# Logic_controller.net
KiCad netlist of a schematic drawn in Altium Designer
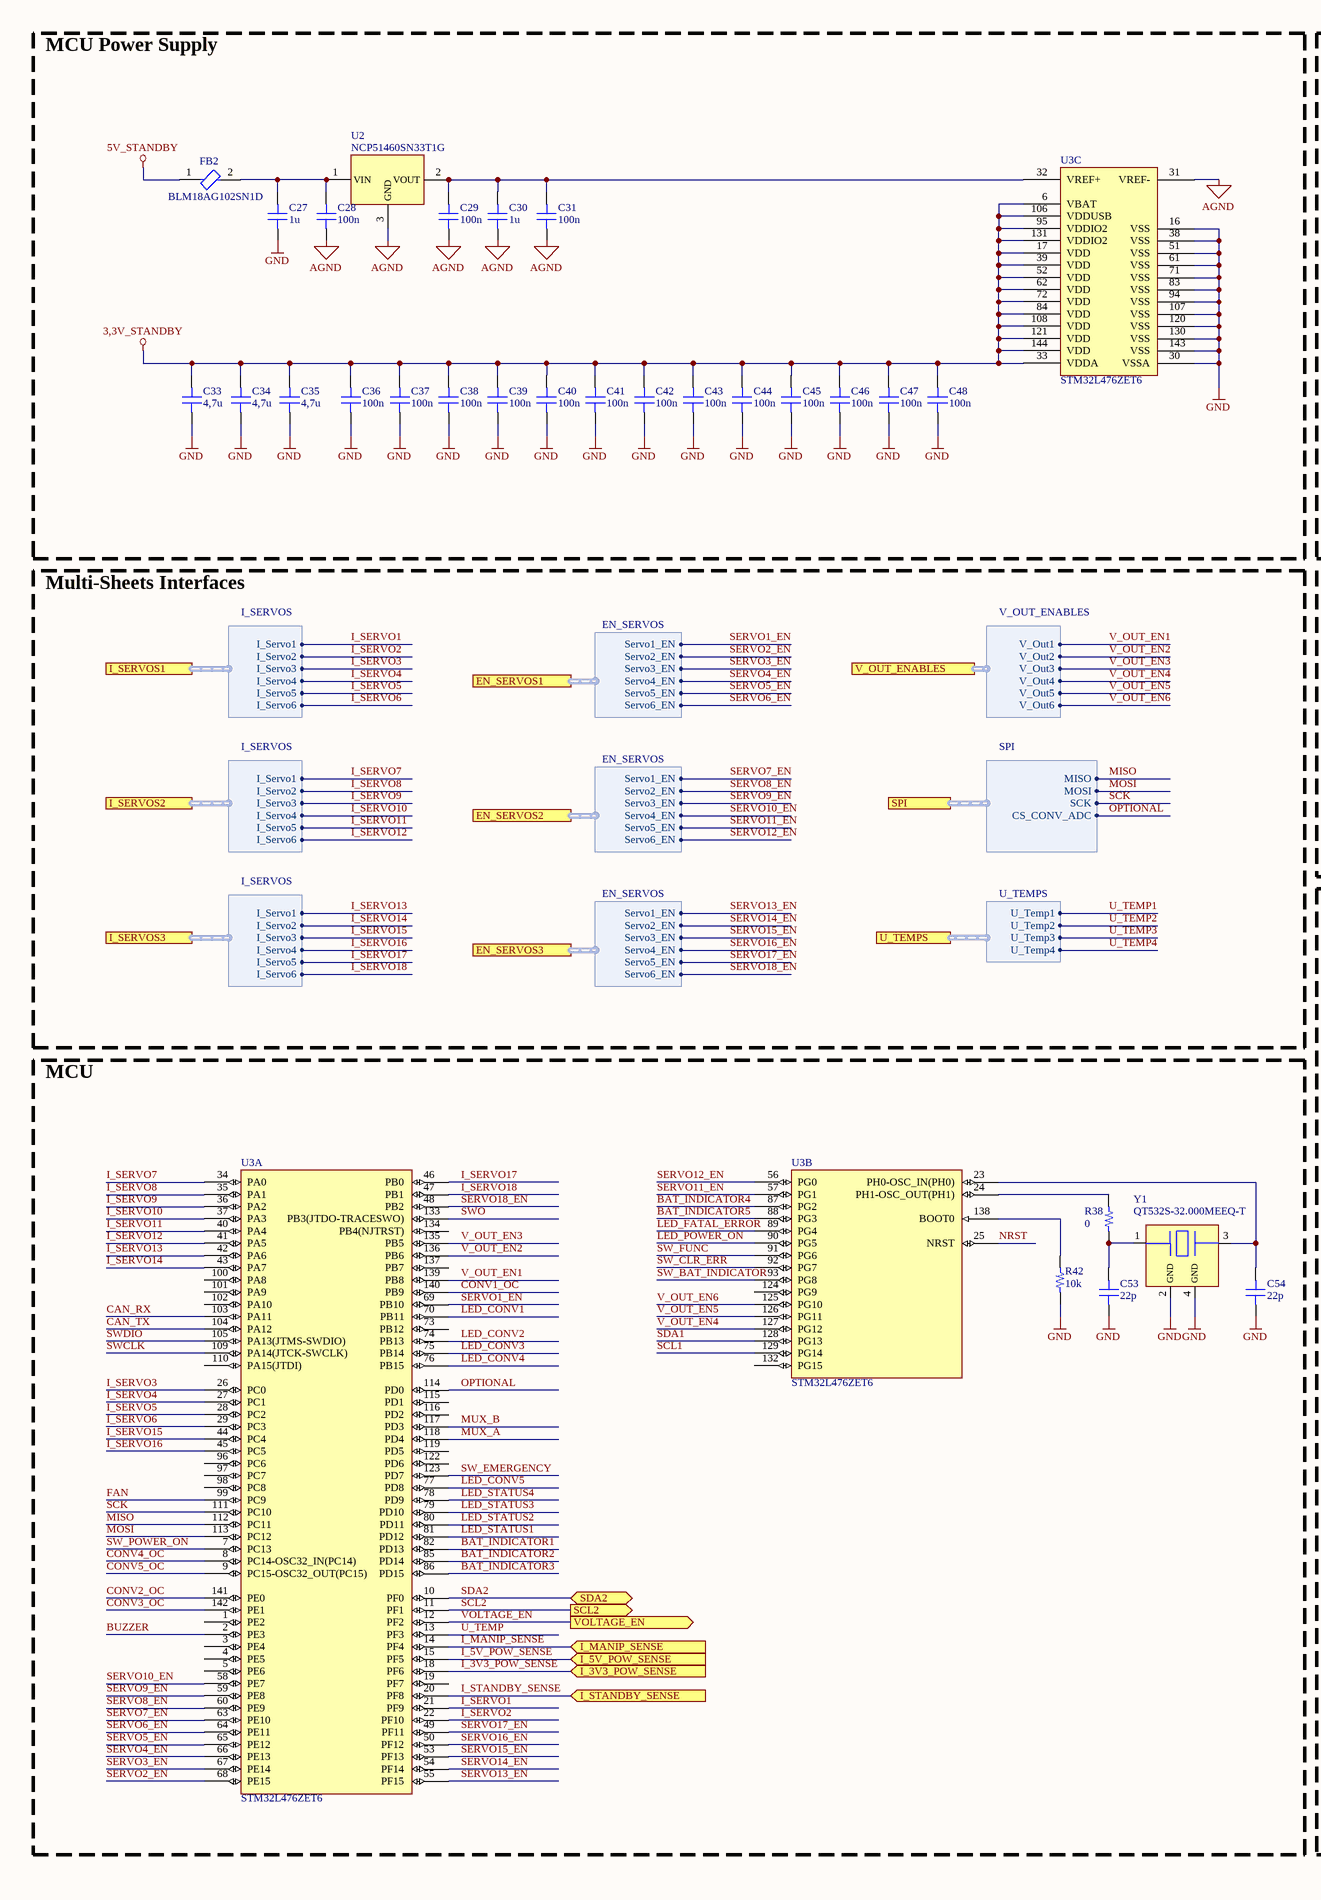
[diagram p0: Logic_controller.SchDoc, left]
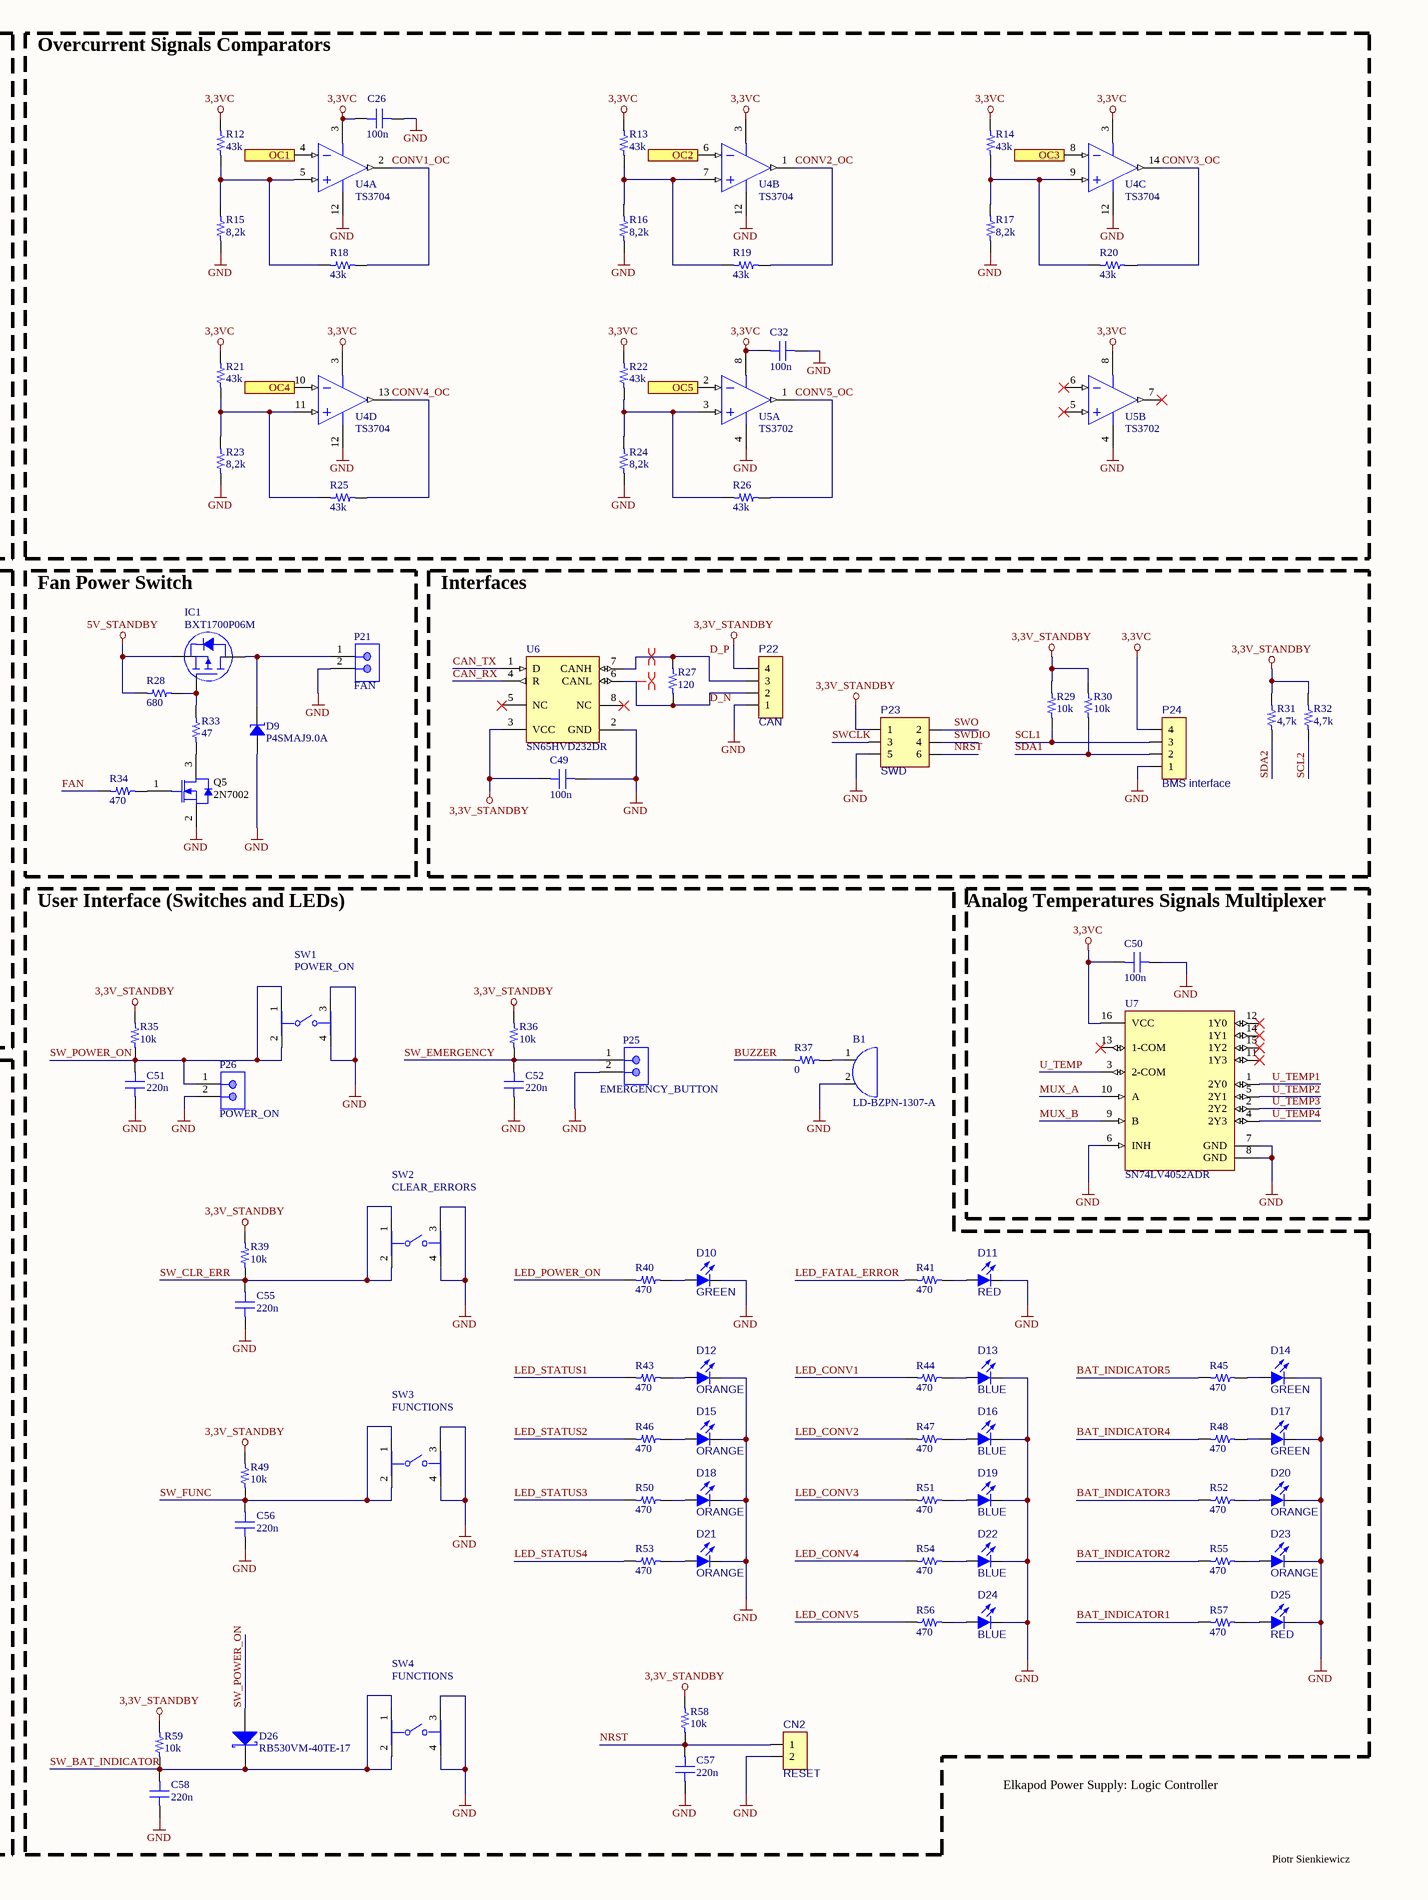
[diagram p1: Logic_controller.SchDoc, right]

(export (version "E")
  (design (tool "Eeschema 10.0.6"))
  (components
    (comp (ref "B1")
      (value "LD-BZPN-1307-A")
      (footprint "LD-BZPN-1307-A")
      (description "12,6mm diameter buzzer without generator; 1-30VAC")
      (libsource (lib "My_passive_components") (part "LD-BZPN-1307-A"))
    )
    (comp (ref "C26")
      (value "100n")
      (footprint "CAP 0603_1608")
      (description "CAP CER 100nF 25V X5R 0603")
      (fields (field (name "PART NUMBER") "C0603C272F3GAC7867") (field (name "MANUFACTURER") "KEMET"))
      (libsource (lib "Celestial Altium Library - altium_library") (part "Capacitor"))
    )
    (comp (ref "C27")
      (value "1u")
      (footprint "CAP 0603_1608")
      (description "CAP CER 1uF 16V X5R 0603")
      (fields (field (name "PART NUMBER") "C0603C272F3GAC7867") (field (name "MANUFACTURER") "KEMET"))
      (libsource (lib "Celestial Altium Library - altium_library") (part "Capacitor"))
    )
    (comp (ref "C28")
      (value "100n")
      (footprint "CAP 0603_1608")
      (description "CAP CER 100nF 25V X5R 0603")
      (fields (field (name "PART NUMBER") "C0603C272F3GAC7867") (field (name "MANUFACTURER") "KEMET"))
      (libsource (lib "Celestial Altium Library - altium_library") (part "Capacitor"))
    )
    (comp (ref "C29")
      (value "100n")
      (footprint "CAP 0603_1608")
      (description "CAP CER 100nF 25V X5R 0603")
      (fields (field (name "PART NUMBER") "C0603C272F3GAC7867") (field (name "MANUFACTURER") "KEMET"))
      (libsource (lib "Celestial Altium Library - altium_library") (part "Capacitor"))
    )
    (comp (ref "C30")
      (value "1u")
      (footprint "CAP 0603_1608")
      (description "CAP CER 1uF 16V X5R 0603")
      (fields (field (name "PART NUMBER") "C0603C272F3GAC7867") (field (name "MANUFACTURER") "KEMET"))
      (libsource (lib "Celestial Altium Library - altium_library") (part "Capacitor"))
    )
    (comp (ref "C31")
      (value "100n")
      (footprint "CAP 0603_1608")
      (description "CAP CER 100nF 25V X5R 0603")
      (fields (field (name "PART NUMBER") "C0603C272F3GAC7867") (field (name "MANUFACTURER") "KEMET"))
      (libsource (lib "Celestial Altium Library - altium_library") (part "Capacitor"))
    )
    (comp (ref "C32")
      (value "100n")
      (footprint "CAP 0603_1608")
      (description "CAP CER 100nF 25V X5R 0603")
      (fields (field (name "PART NUMBER") "C0603C272F3GAC7867") (field (name "MANUFACTURER") "KEMET"))
      (libsource (lib "Celestial Altium Library - altium_library") (part "Capacitor"))
    )
    (comp (ref "C33")
      (value "4,7u")
      (footprint "CAP 0603_1608")
      (description "CAP CER 4,7uF 25V X5R 0603")
      (fields (field (name "PART NUMBER") "C0603C272F3GAC7867") (field (name "MANUFACTURER") "KEMET"))
      (libsource (lib "Celestial Altium Library - altium_library") (part "Capacitor"))
    )
    (comp (ref "C34")
      (value "4,7u")
      (footprint "CAP 0603_1608")
      (description "CAP CER 4,7uF 25V X5R 0603")
      (fields (field (name "PART NUMBER") "C0603C272F3GAC7867") (field (name "MANUFACTURER") "KEMET"))
      (libsource (lib "Celestial Altium Library - altium_library") (part "Capacitor"))
    )
    (comp (ref "C35")
      (value "4,7u")
      (footprint "CAP 0603_1608")
      (description "CAP CER 4,7uF 25V X5R 0603")
      (fields (field (name "PART NUMBER") "C0603C272F3GAC7867") (field (name "MANUFACTURER") "KEMET"))
      (libsource (lib "Celestial Altium Library - altium_library") (part "Capacitor"))
    )
    (comp (ref "C36")
      (value "100n")
      (footprint "CAP 0603_1608")
      (description "CAP CER 100nF 25V X5R 0603")
      (fields (field (name "PART NUMBER") "C0603C272F3GAC7867") (field (name "MANUFACTURER") "KEMET"))
      (libsource (lib "Celestial Altium Library - altium_library") (part "Capacitor"))
    )
    (comp (ref "C37")
      (value "100n")
      (footprint "CAP 0603_1608")
      (description "CAP CER 100nF 25V X5R 0603")
      (fields (field (name "PART NUMBER") "C0603C272F3GAC7867") (field (name "MANUFACTURER") "KEMET"))
      (libsource (lib "Celestial Altium Library - altium_library") (part "Capacitor"))
    )
    (comp (ref "C38")
      (value "100n")
      (footprint "CAP 0603_1608")
      (description "CAP CER 100nF 25V X5R 0603")
      (fields (field (name "PART NUMBER") "C0603C272F3GAC7867") (field (name "MANUFACTURER") "KEMET"))
      (libsource (lib "Celestial Altium Library - altium_library") (part "Capacitor"))
    )
    (comp (ref "C39")
      (value "100n")
      (footprint "CAP 0603_1608")
      (description "CAP CER 100nF 25V X5R 0603")
      (fields (field (name "PART NUMBER") "C0603C272F3GAC7867") (field (name "MANUFACTURER") "KEMET"))
      (libsource (lib "Celestial Altium Library - altium_library") (part "Capacitor"))
    )
    (comp (ref "C40")
      (value "100n")
      (footprint "CAP 0603_1608")
      (description "CAP CER 100nF 25V X5R 0603")
      (fields (field (name "PART NUMBER") "C0603C272F3GAC7867") (field (name "MANUFACTURER") "KEMET"))
      (libsource (lib "Celestial Altium Library - altium_library") (part "Capacitor"))
    )
    (comp (ref "C41")
      (value "100n")
      (footprint "CAP 0603_1608")
      (description "CAP CER 100nF 25V X5R 0603")
      (fields (field (name "PART NUMBER") "C0603C272F3GAC7867") (field (name "MANUFACTURER") "KEMET"))
      (libsource (lib "Celestial Altium Library - altium_library") (part "Capacitor"))
    )
    (comp (ref "C42")
      (value "100n")
      (footprint "CAP 0603_1608")
      (description "CAP CER 100nF 25V X5R 0603")
      (fields (field (name "PART NUMBER") "C0603C272F3GAC7867") (field (name "MANUFACTURER") "KEMET"))
      (libsource (lib "Celestial Altium Library - altium_library") (part "Capacitor"))
    )
    (comp (ref "C43")
      (value "100n")
      (footprint "CAP 0603_1608")
      (description "CAP CER 100nF 25V X5R 0603")
      (fields (field (name "PART NUMBER") "C0603C272F3GAC7867") (field (name "MANUFACTURER") "KEMET"))
      (libsource (lib "Celestial Altium Library - altium_library") (part "Capacitor"))
    )
    (comp (ref "C44")
      (value "100n")
      (footprint "CAP 0603_1608")
      (description "CAP CER 100nF 25V X5R 0603")
      (fields (field (name "PART NUMBER") "C0603C272F3GAC7867") (field (name "MANUFACTURER") "KEMET"))
      (libsource (lib "Celestial Altium Library - altium_library") (part "Capacitor"))
    )
    (comp (ref "C45")
      (value "100n")
      (footprint "CAP 0603_1608")
      (description "CAP CER 100nF 25V X5R 0603")
      (fields (field (name "PART NUMBER") "C0603C272F3GAC7867") (field (name "MANUFACTURER") "KEMET"))
      (libsource (lib "Celestial Altium Library - altium_library") (part "Capacitor"))
    )
    (comp (ref "C46")
      (value "100n")
      (footprint "CAP 0603_1608")
      (description "CAP CER 100nF 25V X5R 0603")
      (fields (field (name "PART NUMBER") "C0603C272F3GAC7867") (field (name "MANUFACTURER") "KEMET"))
      (libsource (lib "Celestial Altium Library - altium_library") (part "Capacitor"))
    )
    (comp (ref "C47")
      (value "100n")
      (footprint "CAP 0603_1608")
      (description "CAP CER 100nF 25V X5R 0603")
      (fields (field (name "PART NUMBER") "C0603C272F3GAC7867") (field (name "MANUFACTURER") "KEMET"))
      (libsource (lib "Celestial Altium Library - altium_library") (part "Capacitor"))
    )
    (comp (ref "C48")
      (value "100n")
      (footprint "CAP 0603_1608")
      (description "CAP CER 100nF 25V X5R 0603")
      (fields (field (name "PART NUMBER") "C0603C272F3GAC7867") (field (name "MANUFACTURER") "KEMET"))
      (libsource (lib "Celestial Altium Library - altium_library") (part "Capacitor"))
    )
    (comp (ref "C49")
      (value "100n")
      (footprint "CAP 0603_1608")
      (description "CAP CER 100nF 25V X5R 0603")
      (fields (field (name "PART NUMBER") "C0603C272F3GAC7867") (field (name "MANUFACTURER") "KEMET"))
      (libsource (lib "Celestial Altium Library - altium_library") (part "Capacitor"))
    )
    (comp (ref "C50")
      (value "100n")
      (footprint "CAP 0603_1608")
      (description "CAP CER 100nF 25V X5R 0603")
      (fields (field (name "PART NUMBER") "C0603C272F3GAC7867") (field (name "MANUFACTURER") "KEMET"))
      (libsource (lib "Celestial Altium Library - altium_library") (part "Capacitor"))
    )
    (comp (ref "C51")
      (value "220n")
      (footprint "CAP 0603_1608")
      (description "CAP CER 220nF 25V X5R 0603")
      (fields (field (name "PART NUMBER") "C0603C272F3GAC7867") (field (name "MANUFACTURER") "KEMET"))
      (libsource (lib "Celestial Altium Library - altium_library") (part "Capacitor"))
    )
    (comp (ref "C52")
      (value "220n")
      (footprint "CAP 0603_1608")
      (description "CAP CER 220nF 25V X5R 0603")
      (fields (field (name "PART NUMBER") "C0603C272F3GAC7867") (field (name "MANUFACTURER") "KEMET"))
      (libsource (lib "Celestial Altium Library - altium_library") (part "Capacitor"))
    )
    (comp (ref "C53")
      (value "22p")
      (footprint "CAP 0603_1608")
      (description "CAP CER 22pF 50V G0C 0603")
      (fields (field (name "PART NUMBER") "C0603C272F3GAC7867") (field (name "MANUFACTURER") "KEMET"))
      (libsource (lib "Celestial Altium Library - altium_library") (part "Capacitor"))
    )
    (comp (ref "C54")
      (value "22p")
      (footprint "CAP 0603_1608")
      (description "CAP CER 22pF 50V G0C 0603")
      (fields (field (name "PART NUMBER") "C0603C272F3GAC7867") (field (name "MANUFACTURER") "KEMET"))
      (libsource (lib "Celestial Altium Library - altium_library") (part "Capacitor"))
    )
    (comp (ref "C55")
      (value "220n")
      (footprint "CAP 0603_1608")
      (description "CAP CER 220nF 25V X5R 0603")
      (fields (field (name "PART NUMBER") "C0603C272F3GAC7867") (field (name "MANUFACTURER") "KEMET"))
      (libsource (lib "Celestial Altium Library - altium_library") (part "Capacitor"))
    )
    (comp (ref "C56")
      (value "220n")
      (footprint "CAP 0603_1608")
      (description "CAP CER 220nF 25V X5R 0603")
      (fields (field (name "PART NUMBER") "C0603C272F3GAC7867") (field (name "MANUFACTURER") "KEMET"))
      (libsource (lib "Celestial Altium Library - altium_library") (part "Capacitor"))
    )
    (comp (ref "C57")
      (value "220n")
      (footprint "CAP 0603_1608")
      (description "CAP CER 220nF 25V X5R 0603")
      (fields (field (name "PART NUMBER") "C0603C272F3GAC7867") (field (name "MANUFACTURER") "KEMET"))
      (libsource (lib "Celestial Altium Library - altium_library") (part "Capacitor"))
    )
    (comp (ref "C58")
      (value "220n")
      (footprint "CAP 0603_1608")
      (description "CAP CER 220nF 25V X5R 0603")
      (fields (field (name "PART NUMBER") "C0603C272F3GAC7867") (field (name "MANUFACTURER") "KEMET"))
      (libsource (lib "Celestial Altium Library - altium_library") (part "Capacitor"))
    )
    (comp (ref "CN2") (value "RESET") (footprint "GP_2x1") (libsource (lib "goldpin_male") (part "CN_2x1")))
    (comp (ref "D9")
      (value "P4SMAJ9.0A")
      (footprint "DO214AC SMA")
      (description "TVS DIODE 9VDC DO214AC")
      (libsource (lib "Celestial Altium Library - altium_library") (part "DIODE TVS UNI"))
    )
    (comp (ref "D10")
      (value "GREEN")
      (footprint "LED0805B")
      (description "GREEN LED")
      (libsource (lib "leds") (part "LED_BLUE"))
    )
    (comp (ref "D11")
      (value "RED")
      (footprint "LED0805B")
      (description "RED LED")
      (libsource (lib "leds") (part "LED_BLUE"))
    )
    (comp (ref "D12")
      (value "ORANGE")
      (footprint "LED0805B")
      (description "ORANGE LED")
      (libsource (lib "leds") (part "LED_BLUE"))
    )
    (comp (ref "D13")
      (value "BLUE")
      (footprint "LED0805B")
      (description "BLUE LED")
      (libsource (lib "leds") (part "LED_BLUE"))
    )
    (comp (ref "D14")
      (value "GREEN")
      (footprint "LED0805B")
      (description "GREEN LED")
      (libsource (lib "leds") (part "LED_BLUE"))
    )
    (comp (ref "D15")
      (value "ORANGE")
      (footprint "LED0805B")
      (description "ORANGE LED")
      (libsource (lib "leds") (part "LED_BLUE"))
    )
    (comp (ref "D16")
      (value "BLUE")
      (footprint "LED0805B")
      (description "BLUE LED")
      (libsource (lib "leds") (part "LED_BLUE"))
    )
    (comp (ref "D17")
      (value "GREEN")
      (footprint "LED0805B")
      (description "GREEN LED")
      (libsource (lib "leds") (part "LED_BLUE"))
    )
    (comp (ref "D18")
      (value "ORANGE")
      (footprint "LED0805B")
      (description "ORANGE LED")
      (libsource (lib "leds") (part "LED_BLUE"))
    )
    (comp (ref "D19")
      (value "BLUE")
      (footprint "LED0805B")
      (description "BLUE LED")
      (libsource (lib "leds") (part "LED_BLUE"))
    )
    (comp (ref "D20")
      (value "ORANGE")
      (footprint "LED0805B")
      (description "ORANGE LED")
      (libsource (lib "leds") (part "LED_BLUE"))
    )
    (comp (ref "D21")
      (value "ORANGE")
      (footprint "LED0805B")
      (description "ORANGE LED")
      (libsource (lib "leds") (part "LED_BLUE"))
    )
    (comp (ref "D22")
      (value "BLUE")
      (footprint "LED0805B")
      (description "BLUE LED")
      (libsource (lib "leds") (part "LED_BLUE"))
    )
    (comp (ref "D23")
      (value "ORANGE")
      (footprint "LED0805B")
      (description "ORANGE LED")
      (libsource (lib "leds") (part "LED_BLUE"))
    )
    (comp (ref "D24")
      (value "BLUE")
      (footprint "LED0805B")
      (description "BLUE LED")
      (libsource (lib "leds") (part "LED_BLUE"))
    )
    (comp (ref "D25")
      (value "RED")
      (footprint "LED0805B")
      (description "RED LED")
      (libsource (lib "leds") (part "LED_BLUE"))
    )
    (comp (ref "D26")
      (value "RB530VM-40TE-17")
      (footprint "SOD-323")
      (description "Schottky diode; 0,1A; 40V")
      (fields (field (name "PUBLISHER") "Altium Limited"))
      (libsource (lib "Infineon Discrete Diode") (part "BAS140W"))
    )
    (comp (ref "FB2")
      (value "BLM18AG102SN1D")
      (footprint "FP-BLM18-0_15-t0_8-MFG")
      (description "Chip Ferrite Bead, 0603, 1000Ω @ 100MHz, 0.5Ω, 25%, 450mA")
      (fields (field (name "TOLERANCE") "25%"))
      (libsource (lib "Altium Content Vault") (part "5f30dd21d616792df468990f7003faa"))
    )
    (comp (ref "IC1")
      (value "BXT1700P06M")
      (footprint "ON SEMI SOT-23-3")
      (description "MOSFET P-CH 60V 2.8A SOT-23-3")
      (libsource (lib "Celestial Altium Library - altium_library") (part "ON SEMI MOSFET P-CH SOT-23-3"))
    )
    (comp (ref "P21")
      (value "FAN")
      (footprint "MOLX-22-23-2021_V")
      (fields (field (name "PARTNUMBER") "22-23-2021"))
      (libsource (lib "Altium Content Vault") (part "CN-1P-M-R2"))
    )
    (comp (ref "P22")
      (value "CAN")
      (footprint "KK/2.54/4")
      (description "Connector: PCB-cable; KK; socket; male; PIN:4; straight/right-angle; tinned; THT")
      (libsource (lib "kk") (part "CN_4x1"))
    )
    (comp (ref "P23") (value "SWD") (footprint "GP_3x2") (libsource (lib "goldpin_male") (part "CN_3x2")))
    (comp (ref "P24")
      (value "BMS interface")
      (footprint "KK/2.54/4")
      (description "Connector: PCB-cable; KK; socket; male; PIN:4; straight/right-angle; tinned; THT")
      (libsource (lib "kk") (part "CN_4x1"))
    )
    (comp (ref "P25")
      (value "EMERGENCY_BUTTON")
      (footprint "MOLX-22-23-2021_V")
      (fields (field (name "PARTNUMBER") "22-23-2021"))
      (libsource (lib "Altium Content Vault") (part "CN-1P-M-R2"))
    )
    (comp (ref "P26")
      (value "POWER_ON")
      (footprint "MOLX-22-23-2021_V")
      (fields (field (name "PARTNUMBER") "22-23-2021"))
      (libsource (lib "Altium Content Vault") (part "CN-1P-M-R2"))
    )
    (comp (ref "Q5")
      (value "2N7002")
      (footprint "INF-PG-SOT23_M")
      (fields (field (name "MANUFACTURER") "Infineon"))
      (libsource (lib "Altium Content Vault") (part "INF-NDMOS-GSD-3"))
    )
    (comp (ref "R12")
      (value "43k")
      (footprint "RES 0603_1608")
      (description "RES 43K OHM 1% 0,1W 0603")
      (fields
        (field (name "PART NUMBER") "RNCS0603BKE10K0")
        (field (name "MANUFACTURER") "Stackpole Electronics Inc")
      )
      (libsource (lib "Celestial Altium Library - altium_library") (part "Resistor"))
    )
    (comp (ref "R13")
      (value "43k")
      (footprint "RES 0603_1608")
      (description "RES 43K OHM 1% 0,1W 0603")
      (fields
        (field (name "PART NUMBER") "RNCS0603BKE10K0")
        (field (name "MANUFACTURER") "Stackpole Electronics Inc")
      )
      (libsource (lib "Celestial Altium Library - altium_library") (part "Resistor"))
    )
    (comp (ref "R14")
      (value "43k")
      (footprint "RES 0603_1608")
      (description "RES 43K OHM 1% 0,1W 0603")
      (fields
        (field (name "PART NUMBER") "RNCS0603BKE10K0")
        (field (name "MANUFACTURER") "Stackpole Electronics Inc")
      )
      (libsource (lib "Celestial Altium Library - altium_library") (part "Resistor"))
    )
    (comp (ref "R15")
      (value "8,2k")
      (footprint "RES 0603_1608")
      (description "RES 8,2K OHM 1% 0,1W 0603")
      (fields
        (field (name "PART NUMBER") "RNCS0603BKE10K0")
        (field (name "MANUFACTURER") "Stackpole Electronics Inc")
      )
      (libsource (lib "Celestial Altium Library - altium_library") (part "Resistor"))
    )
    (comp (ref "R16")
      (value "8,2k")
      (footprint "RES 0603_1608")
      (description "RES 8,2K OHM 1% 0,1W 0603")
      (fields
        (field (name "PART NUMBER") "RNCS0603BKE10K0")
        (field (name "MANUFACTURER") "Stackpole Electronics Inc")
      )
      (libsource (lib "Celestial Altium Library - altium_library") (part "Resistor"))
    )
    (comp (ref "R17")
      (value "8,2k")
      (footprint "RES 0603_1608")
      (description "RES 8,2K OHM 1% 0,1W 0603")
      (fields
        (field (name "PART NUMBER") "RNCS0603BKE10K0")
        (field (name "MANUFACTURER") "Stackpole Electronics Inc")
      )
      (libsource (lib "Celestial Altium Library - altium_library") (part "Resistor"))
    )
    (comp (ref "R18")
      (value "43k")
      (footprint "RES 0603_1608")
      (description "RES 43K OHM 1% 0,1W 0603")
      (fields
        (field (name "PART NUMBER") "RNCS0603BKE10K0")
        (field (name "MANUFACTURER") "Stackpole Electronics Inc")
      )
      (libsource (lib "Celestial Altium Library - altium_library") (part "Resistor"))
    )
    (comp (ref "R19")
      (value "43k")
      (footprint "RES 0603_1608")
      (description "RES 43K OHM 1% 0,1W 0603")
      (fields
        (field (name "PART NUMBER") "RNCS0603BKE10K0")
        (field (name "MANUFACTURER") "Stackpole Electronics Inc")
      )
      (libsource (lib "Celestial Altium Library - altium_library") (part "Resistor"))
    )
    (comp (ref "R20")
      (value "43k")
      (footprint "RES 0603_1608")
      (description "RES 43K OHM 1% 0,1W 0603")
      (fields
        (field (name "PART NUMBER") "RNCS0603BKE10K0")
        (field (name "MANUFACTURER") "Stackpole Electronics Inc")
      )
      (libsource (lib "Celestial Altium Library - altium_library") (part "Resistor"))
    )
    (comp (ref "R21")
      (value "43k")
      (footprint "RES 0603_1608")
      (description "RES 43K OHM 1% 0,1W 0603")
      (fields
        (field (name "PART NUMBER") "RNCS0603BKE10K0")
        (field (name "MANUFACTURER") "Stackpole Electronics Inc")
      )
      (libsource (lib "Celestial Altium Library - altium_library") (part "Resistor"))
    )
    (comp (ref "R22")
      (value "43k")
      (footprint "RES 0603_1608")
      (description "RES 43K OHM 1% 0,1W 0603")
      (fields
        (field (name "PART NUMBER") "RNCS0603BKE10K0")
        (field (name "MANUFACTURER") "Stackpole Electronics Inc")
      )
      (libsource (lib "Celestial Altium Library - altium_library") (part "Resistor"))
    )
    (comp (ref "R23")
      (value "8,2k")
      (footprint "RES 0603_1608")
      (description "RES 8,2K OHM 1% 0,1W 0603")
      (fields
        (field (name "PART NUMBER") "RNCS0603BKE10K0")
        (field (name "MANUFACTURER") "Stackpole Electronics Inc")
      )
      (libsource (lib "Celestial Altium Library - altium_library") (part "Resistor"))
    )
    (comp (ref "R24")
      (value "8,2k")
      (footprint "RES 0603_1608")
      (description "RES 8,2K OHM 1% 0,1W 0603")
      (fields
        (field (name "PART NUMBER") "RNCS0603BKE10K0")
        (field (name "MANUFACTURER") "Stackpole Electronics Inc")
      )
      (libsource (lib "Celestial Altium Library - altium_library") (part "Resistor"))
    )
    (comp (ref "R25")
      (value "43k")
      (footprint "RES 0603_1608")
      (description "RES 43K OHM 1% 0,1W 0603")
      (fields
        (field (name "PART NUMBER") "RNCS0603BKE10K0")
        (field (name "MANUFACTURER") "Stackpole Electronics Inc")
      )
      (libsource (lib "Celestial Altium Library - altium_library") (part "Resistor"))
    )
    (comp (ref "R26")
      (value "43k")
      (footprint "RES 0603_1608")
      (description "RES 43K OHM 1% 0,1W 0603")
      (fields
        (field (name "PART NUMBER") "RNCS0603BKE10K0")
        (field (name "MANUFACTURER") "Stackpole Electronics Inc")
      )
      (libsource (lib "Celestial Altium Library - altium_library") (part "Resistor"))
    )
    (comp (ref "R27")
      (value "120")
      (footprint "RES 0603_1608")
      (description "RES 120 OHM 1% 0,1W 0603")
      (fields
        (field (name "PART NUMBER") "RNCS0603BKE10K0")
        (field (name "MANUFACTURER") "Stackpole Electronics Inc")
      )
      (libsource (lib "Celestial Altium Library - altium_library") (part "Resistor"))
    )
    (comp (ref "R28")
      (value "680")
      (footprint "RES 0603_1608")
      (description "RES 680 OHM 1% 0,1W 0603")
      (fields
        (field (name "PART NUMBER") "RNCS0603BKE10K0")
        (field (name "MANUFACTURER") "Stackpole Electronics Inc")
      )
      (libsource (lib "Celestial Altium Library - altium_library") (part "Resistor"))
    )
    (comp (ref "R29")
      (value "10k")
      (footprint "RES 0603_1608")
      (description "RES 10K OHM 1% 0,1W 0603")
      (fields
        (field (name "PART NUMBER") "RNCS0603BKE10K0")
        (field (name "MANUFACTURER") "Stackpole Electronics Inc")
      )
      (libsource (lib "Celestial Altium Library - altium_library") (part "Resistor"))
    )
    (comp (ref "R30")
      (value "10k")
      (footprint "RES 0603_1608")
      (description "RES 10K OHM 1% 0,1W 0603")
      (fields
        (field (name "PART NUMBER") "RNCS0603BKE10K0")
        (field (name "MANUFACTURER") "Stackpole Electronics Inc")
      )
      (libsource (lib "Celestial Altium Library - altium_library") (part "Resistor"))
    )
    (comp (ref "R31")
      (value "4,7k")
      (footprint "RES 0603_1608")
      (description "RES 4,7K OHM 1% 0,1W 0603")
      (fields
        (field (name "PART NUMBER") "RNCS0603BKE10K0")
        (field (name "MANUFACTURER") "Stackpole Electronics Inc")
      )
      (libsource (lib "Celestial Altium Library - altium_library") (part "Resistor"))
    )
    (comp (ref "R32")
      (value "4,7k")
      (footprint "RES 0603_1608")
      (description "RES 4,7K OHM 1% 0,1W 0603")
      (fields
        (field (name "PART NUMBER") "RNCS0603BKE10K0")
        (field (name "MANUFACTURER") "Stackpole Electronics Inc")
      )
      (libsource (lib "Celestial Altium Library - altium_library") (part "Resistor"))
    )
    (comp (ref "R33")
      (value "47")
      (footprint "RES 0603_1608")
      (description "RES 47 OHM 1% 0,1W 0603")
      (fields
        (field (name "PART NUMBER") "RNCS0603BKE10K0")
        (field (name "MANUFACTURER") "Stackpole Electronics Inc")
      )
      (libsource (lib "Celestial Altium Library - altium_library") (part "Resistor"))
    )
    (comp (ref "R34")
      (value "470")
      (footprint "RES 0603_1608")
      (description "RES 470 OHM 1% 0,1W 0603")
      (fields
        (field (name "PART NUMBER") "RNCS0603BKE10K0")
        (field (name "MANUFACTURER") "Stackpole Electronics Inc")
      )
      (libsource (lib "Celestial Altium Library - altium_library") (part "Resistor"))
    )
    (comp (ref "R35")
      (value "10k")
      (footprint "RES 0603_1608")
      (description "RES 10K OHM 1% 0,1W 0603")
      (fields
        (field (name "PART NUMBER") "RNCS0603BKE10K0")
        (field (name "MANUFACTURER") "Stackpole Electronics Inc")
      )
      (libsource (lib "Celestial Altium Library - altium_library") (part "Resistor"))
    )
    (comp (ref "R36")
      (value "10k")
      (footprint "RES 0603_1608")
      (description "RES 10K OHM 1% 0,1W 0603")
      (fields
        (field (name "PART NUMBER") "RNCS0603BKE10K0")
        (field (name "MANUFACTURER") "Stackpole Electronics Inc")
      )
      (libsource (lib "Celestial Altium Library - altium_library") (part "Resistor"))
    )
    (comp (ref "R37")
      (value "0")
      (footprint "RES 0603_1608")
      (description "RES 0 OHM 1% 0,1W 0603")
      (fields
        (field (name "PART NUMBER") "RNCS0603BKE10K0")
        (field (name "MANUFACTURER") "Stackpole Electronics Inc")
      )
      (libsource (lib "Celestial Altium Library - altium_library") (part "Resistor"))
    )
    (comp (ref "R38")
      (value "0")
      (footprint "RES 0603_1608")
      (description "RES 0 OHM 1% 0,1W 0603")
      (fields
        (field (name "PART NUMBER") "RNCS0603BKE10K0")
        (field (name "MANUFACTURER") "Stackpole Electronics Inc")
      )
      (libsource (lib "Celestial Altium Library - altium_library") (part "Resistor"))
    )
    (comp (ref "R39")
      (value "10k")
      (footprint "RES 0603_1608")
      (description "RES 10K OHM 1% 0,1W 0603")
      (fields
        (field (name "PART NUMBER") "RNCS0603BKE10K0")
        (field (name "MANUFACTURER") "Stackpole Electronics Inc")
      )
      (libsource (lib "Celestial Altium Library - altium_library") (part "Resistor"))
    )
    (comp (ref "R40")
      (value "470")
      (footprint "RES 0603_1608")
      (description "RES 470 OHM 1% 0,1W 0603")
      (fields
        (field (name "PART NUMBER") "RNCS0603BKE10K0")
        (field (name "MANUFACTURER") "Stackpole Electronics Inc")
      )
      (libsource (lib "Celestial Altium Library - altium_library") (part "Resistor"))
    )
    (comp (ref "R41")
      (value "470")
      (footprint "RES 0603_1608")
      (description "RES 470 OHM 1% 0,1W 0603")
      (fields
        (field (name "PART NUMBER") "RNCS0603BKE10K0")
        (field (name "MANUFACTURER") "Stackpole Electronics Inc")
      )
      (libsource (lib "Celestial Altium Library - altium_library") (part "Resistor"))
    )
    (comp (ref "R42")
      (value "10k")
      (footprint "RES 0603_1608")
      (description "RES 10K OHM 1% 0,1W 0603")
      (fields
        (field (name "PART NUMBER") "RNCS0603BKE10K0")
        (field (name "MANUFACTURER") "Stackpole Electronics Inc")
      )
      (libsource (lib "Celestial Altium Library - altium_library") (part "Resistor"))
    )
    (comp (ref "R43")
      (value "470")
      (footprint "RES 0603_1608")
      (description "RES 470 OHM 1% 0,1W 0603")
      (fields
        (field (name "PART NUMBER") "RNCS0603BKE10K0")
        (field (name "MANUFACTURER") "Stackpole Electronics Inc")
      )
      (libsource (lib "Celestial Altium Library - altium_library") (part "Resistor"))
    )
    (comp (ref "R44")
      (value "470")
      (footprint "RES 0603_1608")
      (description "RES 470 OHM 1% 0,1W 0603")
      (fields
        (field (name "PART NUMBER") "RNCS0603BKE10K0")
        (field (name "MANUFACTURER") "Stackpole Electronics Inc")
      )
      (libsource (lib "Celestial Altium Library - altium_library") (part "Resistor"))
    )
    (comp (ref "R45")
      (value "470")
      (footprint "RES 0603_1608")
      (description "RES 470 OHM 1% 0,1W 0603")
      (fields
        (field (name "PART NUMBER") "RNCS0603BKE10K0")
        (field (name "MANUFACTURER") "Stackpole Electronics Inc")
      )
      (libsource (lib "Celestial Altium Library - altium_library") (part "Resistor"))
    )
    (comp (ref "R46")
      (value "470")
      (footprint "RES 0603_1608")
      (description "RES 470 OHM 1% 0,1W 0603")
      (fields
        (field (name "PART NUMBER") "RNCS0603BKE10K0")
        (field (name "MANUFACTURER") "Stackpole Electronics Inc")
      )
      (libsource (lib "Celestial Altium Library - altium_library") (part "Resistor"))
    )
    (comp (ref "R47")
      (value "470")
      (footprint "RES 0603_1608")
      (description "RES 470 OHM 1% 0,1W 0603")
      (fields
        (field (name "PART NUMBER") "RNCS0603BKE10K0")
        (field (name "MANUFACTURER") "Stackpole Electronics Inc")
      )
      (libsource (lib "Celestial Altium Library - altium_library") (part "Resistor"))
    )
    (comp (ref "R48")
      (value "470")
      (footprint "RES 0603_1608")
      (description "RES 470 OHM 1% 0,1W 0603")
      (fields
        (field (name "PART NUMBER") "RNCS0603BKE10K0")
        (field (name "MANUFACTURER") "Stackpole Electronics Inc")
      )
      (libsource (lib "Celestial Altium Library - altium_library") (part "Resistor"))
    )
    (comp (ref "R49")
      (value "10k")
      (footprint "RES 0603_1608")
      (description "RES 10K OHM 1% 0,1W 0603")
      (fields
        (field (name "PART NUMBER") "RNCS0603BKE10K0")
        (field (name "MANUFACTURER") "Stackpole Electronics Inc")
      )
      (libsource (lib "Celestial Altium Library - altium_library") (part "Resistor"))
    )
    (comp (ref "R50")
      (value "470")
      (footprint "RES 0603_1608")
      (description "RES 470 OHM 1% 0,1W 0603")
      (fields
        (field (name "PART NUMBER") "RNCS0603BKE10K0")
        (field (name "MANUFACTURER") "Stackpole Electronics Inc")
      )
      (libsource (lib "Celestial Altium Library - altium_library") (part "Resistor"))
    )
    (comp (ref "R51")
      (value "470")
      (footprint "RES 0603_1608")
      (description "RES 470 OHM 1% 0,1W 0603")
      (fields
        (field (name "PART NUMBER") "RNCS0603BKE10K0")
        (field (name "MANUFACTURER") "Stackpole Electronics Inc")
      )
      (libsource (lib "Celestial Altium Library - altium_library") (part "Resistor"))
    )
    (comp (ref "R52")
      (value "470")
      (footprint "RES 0603_1608")
      (description "RES 470 OHM 1% 0,1W 0603")
      (fields
        (field (name "PART NUMBER") "RNCS0603BKE10K0")
        (field (name "MANUFACTURER") "Stackpole Electronics Inc")
      )
      (libsource (lib "Celestial Altium Library - altium_library") (part "Resistor"))
    )
    (comp (ref "R53")
      (value "470")
      (footprint "RES 0603_1608")
      (description "RES 470 OHM 1% 0,1W 0603")
      (fields
        (field (name "PART NUMBER") "RNCS0603BKE10K0")
        (field (name "MANUFACTURER") "Stackpole Electronics Inc")
      )
      (libsource (lib "Celestial Altium Library - altium_library") (part "Resistor"))
    )
    (comp (ref "R54")
      (value "470")
      (footprint "RES 0603_1608")
      (description "RES 470 OHM 1% 0,1W 0603")
      (fields
        (field (name "PART NUMBER") "RNCS0603BKE10K0")
        (field (name "MANUFACTURER") "Stackpole Electronics Inc")
      )
      (libsource (lib "Celestial Altium Library - altium_library") (part "Resistor"))
    )
    (comp (ref "R55")
      (value "470")
      (footprint "RES 0603_1608")
      (description "RES 470 OHM 1% 0,1W 0603")
      (fields
        (field (name "PART NUMBER") "RNCS0603BKE10K0")
        (field (name "MANUFACTURER") "Stackpole Electronics Inc")
      )
      (libsource (lib "Celestial Altium Library - altium_library") (part "Resistor"))
    )
    (comp (ref "R56")
      (value "470")
      (footprint "RES 0603_1608")
      (description "RES 470 OHM 1% 0,1W 0603")
      (fields
        (field (name "PART NUMBER") "RNCS0603BKE10K0")
        (field (name "MANUFACTURER") "Stackpole Electronics Inc")
      )
      (libsource (lib "Celestial Altium Library - altium_library") (part "Resistor"))
    )
    (comp (ref "R57")
      (value "470")
      (footprint "RES 0603_1608")
      (description "RES 470 OHM 1% 0,1W 0603")
      (fields
        (field (name "PART NUMBER") "RNCS0603BKE10K0")
        (field (name "MANUFACTURER") "Stackpole Electronics Inc")
      )
      (libsource (lib "Celestial Altium Library - altium_library") (part "Resistor"))
    )
    (comp (ref "R58")
      (value "10k")
      (footprint "RES 0603_1608")
      (description "RES 10K OHM 1% 0,1W 0603")
      (fields
        (field (name "PART NUMBER") "RNCS0603BKE10K0")
        (field (name "MANUFACTURER") "Stackpole Electronics Inc")
      )
      (libsource (lib "Celestial Altium Library - altium_library") (part "Resistor"))
    )
    (comp (ref "R59")
      (value "10k")
      (footprint "RES 0603_1608")
      (description "RES 10K OHM 1% 0,1W 0603")
      (fields
        (field (name "PART NUMBER") "RNCS0603BKE10K0")
        (field (name "MANUFACTURER") "Stackpole Electronics Inc")
      )
      (libsource (lib "Celestial Altium Library - altium_library") (part "Resistor"))
    )
    (comp (ref "SW1")
      (value "POWER_ON")
      (footprint "FP-B3FS-1000-MFG")
      (description "SWITCH TACTILE SPST-NO 0.05A 24V")
      (fields
        (field (name "MANUFACTURER") "Omron Electronics Inc-EMC Div")
        (field (name "OCTOPART") "https://octopart.com/b3fs-1000-omron-116581")
      )
      (libsource (lib "Altium Content Vault") (part "b8895f3f4cefb76e1819d2863dba89b"))
    )
    (comp (ref "SW2")
      (value "CLEAR_ERRORS")
      (footprint "FP-B3FS-1000-MFG")
      (description "SWITCH TACTILE SPST-NO 0.05A 24V")
      (fields
        (field (name "MANUFACTURER") "Omron Electronics Inc-EMC Div")
        (field (name "OCTOPART") "https://octopart.com/b3fs-1000-omron-116581")
      )
      (libsource (lib "Altium Content Vault") (part "b8895f3f4cefb76e1819d2863dba89b"))
    )
    (comp (ref "SW3")
      (value "FUNCTIONS")
      (footprint "FP-B3FS-1000-MFG")
      (description "SWITCH TACTILE SPST-NO 0.05A 24V")
      (fields
        (field (name "MANUFACTURER") "Omron Electronics Inc-EMC Div")
        (field (name "OCTOPART") "https://octopart.com/b3fs-1000-omron-116581")
      )
      (libsource (lib "Altium Content Vault") (part "b8895f3f4cefb76e1819d2863dba89b"))
    )
    (comp (ref "SW4")
      (value "FUNCTIONS")
      (footprint "FP-B3FS-1000-MFG")
      (description "SWITCH TACTILE SPST-NO 0.05A 24V")
      (fields
        (field (name "MANUFACTURER") "Omron Electronics Inc-EMC Div")
        (field (name "OCTOPART") "https://octopart.com/b3fs-1000-omron-116581")
      )
      (libsource (lib "Altium Content Vault") (part "b8895f3f4cefb76e1819d2863dba89b"))
    )
    (comp (ref "U2")
      (value "NCP51460SN33T1G")
      (footprint "SOT23-3")
      (description "Low power precision voltage reference; Iout = 20mA")
      (libsource (lib "My_voltage_regulators") (part "NCP51460SN33T1G"))
    )
    (comp (ref "U3")
      (value "STM32L476ZET6")
      (footprint "STM-LQFP144_M")
      (fields (field (name "MANUFACTURER") "STMicroelectronics"))
      (libsource (lib "Altium Content Vault") (part "MC-ARM-STM32L4X6-LQFP144"))
    )
    (comp (ref "U4")
      (value "TS3704")
      (footprint "SOIC14")
      (description "Micropower push-pusll quad CMOS voltage comparator")
      (libsource (lib "My_integrated_circuits") (part "TS3704"))
    )
    (comp (ref "U5")
      (value "TS3702")
      (footprint "SOIC8")
      (description "Micropower push-pull dual CMOS voltage comparator")
      (libsource (lib "My_integrated_circuits") (part "TS3702"))
    )
    (comp (ref "U6")
      (value "SN65HVD232DR")
      (footprint "D0008A_M")
      (description "3.3 V Can Transceiver, 17 mA, -40 to 85 degC, 8-pin SOIC (D), Green (RoHS & no Sb/Br)")
      (fields (field (name "MANUFACTURER") "Texas Instruments"))
      (libsource (lib "Altium Content Vault") (part "TI-SN65HVD232-SOIC_D-8"))
    )
    (comp (ref "U7")
      (value "SN74LV4052ADR")
      (footprint "FP-D0016A-IPC_B")
      (description "IC MULTIPLEXER DUAL 4X1 16SOIC")
      (libsource (lib "Altium Content Vault") (part "1d2634ae6b0fec4cd987bcefd96d63e"))
    )
    (comp (ref "Y1")
      (value "QT532S-32.000MEEQ-T")
      (footprint "QT532S_5,0x3,2_crystal")
      (libsource (lib "My_passive_components") (part "QT532S_CRYSTAL"))
    )
  )
  (nets
    (net (code "6") (name "/BAT_INDICATOR1") (class "Default")
      (node (ref "R57") (pin "2") (pinfunction "2_2") (pintype "passive"))
      (node (ref "U3") (pin "82") (pinfunction "PD13_82") (pintype "bidirectional"))
    )
    (net (code "7") (name "/BAT_INDICATOR2") (class "Default")
      (node (ref "R55") (pin "2") (pinfunction "2_2") (pintype "passive"))
      (node (ref "U3") (pin "85") (pinfunction "PD14_85") (pintype "bidirectional"))
    )
    (net (code "8") (name "/BAT_INDICATOR3") (class "Default")
      (node (ref "R52") (pin "2") (pinfunction "2_2") (pintype "passive"))
      (node (ref "U3") (pin "86") (pinfunction "PD15_86") (pintype "bidirectional"))
    )
    (net (code "9") (name "/BAT_INDICATOR4") (class "Default")
      (node (ref "R48") (pin "2") (pinfunction "2_2") (pintype "passive"))
      (node (ref "U3") (pin "87") (pinfunction "PG2_87") (pintype "bidirectional"))
    )
    (net (code "10") (name "/BAT_INDICATOR5") (class "Default")
      (node (ref "R45") (pin "2") (pinfunction "2_2") (pintype "passive"))
      (node (ref "U3") (pin "88") (pinfunction "PG3_88") (pintype "bidirectional"))
    )
    (net (code "11") (name "/BUZZER") (class "Default")
      (node (ref "R37") (pin "1") (pinfunction "1_1") (pintype "passive"))
      (node (ref "U3") (pin "2") (pinfunction "PE3_2") (pintype "bidirectional"))
    )
    (net (code "12") (name "/CAN_RX") (class "Default")
      (node (ref "U3") (pin "103") (pinfunction "PA11_103") (pintype "bidirectional"))
      (node (ref "U6") (pin "4") (pinfunction "R_4") (pintype "output"))
    )
    (net (code "13") (name "/CAN_TX") (class "Default")
      (node (ref "U3") (pin "104") (pinfunction "PA12_104") (pintype "bidirectional"))
      (node (ref "U6") (pin "1") (pinfunction "D_1") (pintype "input"))
    )
    (net (code "14") (name "/CONV1_OC") (class "Default")
      (node (ref "R18") (pin "2") (pinfunction "2_2") (pintype "passive"))
      (node (ref "U3") (pin "140") (pinfunction "PB9_140") (pintype "bidirectional"))
      (node (ref "U4") (pin "2") (pinfunction "OUT1_2") (pintype "output"))
    )
    (net (code "15") (name "/CONV2_OC") (class "Default")
      (node (ref "R19") (pin "1") (pinfunction "1_1") (pintype "passive"))
      (node (ref "U3") (pin "141") (pinfunction "PE0_141") (pintype "bidirectional"))
      (node (ref "U4") (pin "1") (pinfunction "OUT2_1") (pintype "output"))
    )
    (net (code "16") (name "/CONV3_OC") (class "Default")
      (node (ref "R20") (pin "1") (pinfunction "1_1") (pintype "passive"))
      (node (ref "U3") (pin "142") (pinfunction "PE1_142") (pintype "bidirectional"))
      (node (ref "U4") (pin "14") (pinfunction "OUT3_14") (pintype "output"))
    )
    (net (code "17") (name "/CONV4_OC") (class "Default")
      (node (ref "R25") (pin "1") (pinfunction "1_1") (pintype "passive"))
      (node (ref "U3") (pin "8") (pinfunction "PC14-OSC32_IN(PC14)_8") (pintype "bidirectional"))
      (node (ref "U4") (pin "13") (pinfunction "OUT4_13") (pintype "output"))
    )
    (net (code "18") (name "/CONV5_OC") (class "Default")
      (node (ref "R26") (pin "1") (pinfunction "1_1") (pintype "passive"))
      (node (ref "U3") (pin "9") (pinfunction "PC15-OSC32_OUT(PC15)_9") (pintype "bidirectional"))
      (node (ref "U5") (pin "1") (pinfunction "OUT1_1") (pintype "output"))
    )
    (net (code "19") (name "/D_N") (class "Default")
      (node (ref "P22") (pin "2") (pinfunction "2_2") (pintype "passive"))
      (node (ref "R27") (pin "2") (pinfunction "2_2") (pintype "passive"))
      (node (ref "U6") (pin "6") (pinfunction "CANL_6") (pintype "bidirectional"))
    )
    (net (code "20") (name "/D_P") (class "Default")
      (node (ref "P22") (pin "3") (pinfunction "3_3") (pintype "passive"))
      (node (ref "R27") (pin "1") (pinfunction "1_1") (pintype "passive"))
      (node (ref "U6") (pin "7") (pinfunction "CANH_7") (pintype "bidirectional"))
    )
    (net (code "21") (name "/FAN") (class "Default")
      (node (ref "R34") (pin "1") (pinfunction "1_1") (pintype "passive"))
      (node (ref "U3") (pin "99") (pinfunction "PC9_99") (pintype "bidirectional"))
    )
    (net (code "22") (name "/I_3V3_POW_SENSE") (class "Default")
      (node (ref "U3") (pin "18") (pinfunction "PF6_18") (pintype "bidirectional"))
    )
    (net (code "23") (name "/I_5V_POW_SENSE") (class "Default")
      (node (ref "U3") (pin "15") (pinfunction "PF5_15") (pintype "bidirectional"))
    )
    (net (code "24") (name "/I_MANIP_SENSE") (class "Default")
      (node (ref "U3") (pin "14") (pinfunction "PF4_14") (pintype "bidirectional"))
    )
    (net (code "25") (name "/I_SERVO1") (class "Default")
      (node (ref "U3") (pin "21") (pinfunction "PF9_21") (pintype "bidirectional"))
    )
    (net (code "26") (name "/I_SERVO2") (class "Default")
      (node (ref "U3") (pin "22") (pinfunction "PF10_22") (pintype "bidirectional"))
    )
    (net (code "27") (name "/I_SERVO3") (class "Default")
      (node (ref "U3") (pin "26") (pinfunction "PC0_26") (pintype "bidirectional"))
    )
    (net (code "28") (name "/I_SERVO4") (class "Default")
      (node (ref "U3") (pin "27") (pinfunction "PC1_27") (pintype "bidirectional"))
    )
    (net (code "29") (name "/I_SERVO5") (class "Default")
      (node (ref "U3") (pin "28") (pinfunction "PC2_28") (pintype "bidirectional"))
    )
    (net (code "30") (name "/I_SERVO6") (class "Default")
      (node (ref "U3") (pin "29") (pinfunction "PC3_29") (pintype "bidirectional"))
    )
    (net (code "31") (name "/I_SERVO7") (class "Default")
      (node (ref "U3") (pin "34") (pinfunction "PA0_34") (pintype "bidirectional"))
    )
    (net (code "32") (name "/I_SERVO8") (class "Default")
      (node (ref "U3") (pin "35") (pinfunction "PA1_35") (pintype "bidirectional"))
    )
    (net (code "33") (name "/I_SERVO9") (class "Default")
      (node (ref "U3") (pin "36") (pinfunction "PA2_36") (pintype "bidirectional"))
    )
    (net (code "34") (name "/I_SERVO10") (class "Default")
      (node (ref "U3") (pin "37") (pinfunction "PA3_37") (pintype "bidirectional"))
    )
    (net (code "35") (name "/I_SERVO11") (class "Default")
      (node (ref "U3") (pin "40") (pinfunction "PA4_40") (pintype "bidirectional"))
    )
    (net (code "36") (name "/I_SERVO12") (class "Default")
      (node (ref "U3") (pin "41") (pinfunction "PA5_41") (pintype "bidirectional"))
    )
    (net (code "37") (name "/I_SERVO13") (class "Default")
      (node (ref "U3") (pin "42") (pinfunction "PA6_42") (pintype "bidirectional"))
    )
    (net (code "38") (name "/I_SERVO14") (class "Default")
      (node (ref "U3") (pin "43") (pinfunction "PA7_43") (pintype "bidirectional"))
    )
    (net (code "39") (name "/I_SERVO15") (class "Default")
      (node (ref "U3") (pin "44") (pinfunction "PC4_44") (pintype "bidirectional"))
    )
    (net (code "40") (name "/I_SERVO16") (class "Default")
      (node (ref "U3") (pin "45") (pinfunction "PC5_45") (pintype "bidirectional"))
    )
    (net (code "41") (name "/I_SERVO17") (class "Default")
      (node (ref "U3") (pin "46") (pinfunction "PB0_46") (pintype "bidirectional"))
    )
    (net (code "42") (name "/I_SERVO18") (class "Default")
      (node (ref "U3") (pin "47") (pinfunction "PB1_47") (pintype "bidirectional"))
    )
    (net (code "43") (name "/I_STANDBY_SENSE") (class "Default")
      (node (ref "U3") (pin "20") (pinfunction "PF8_20") (pintype "bidirectional"))
    )
    (net (code "44") (name "/LED_CONV1") (class "Default")
      (node (ref "R44") (pin "2") (pinfunction "2_2") (pintype "passive"))
      (node (ref "U3") (pin "70") (pinfunction "PB11_70") (pintype "bidirectional"))
    )
    (net (code "45") (name "/LED_CONV2") (class "Default")
      (node (ref "R47") (pin "2") (pinfunction "2_2") (pintype "passive"))
      (node (ref "U3") (pin "74") (pinfunction "PB13_74") (pintype "bidirectional"))
    )
    (net (code "46") (name "/LED_CONV3") (class "Default")
      (node (ref "R51") (pin "2") (pinfunction "2_2") (pintype "passive"))
      (node (ref "U3") (pin "75") (pinfunction "PB14_75") (pintype "bidirectional"))
    )
    (net (code "47") (name "/LED_CONV4") (class "Default")
      (node (ref "R54") (pin "2") (pinfunction "2_2") (pintype "passive"))
      (node (ref "U3") (pin "76") (pinfunction "PB15_76") (pintype "bidirectional"))
    )
    (net (code "48") (name "/LED_CONV5") (class "Default")
      (node (ref "R56") (pin "2") (pinfunction "2_2") (pintype "passive"))
      (node (ref "U3") (pin "77") (pinfunction "PD8_77") (pintype "bidirectional"))
    )
    (net (code "49") (name "/LED_FATAL_ERROR") (class "Default")
      (node (ref "R41") (pin "2") (pinfunction "2_2") (pintype "passive"))
      (node (ref "U3") (pin "89") (pinfunction "PG4_89") (pintype "bidirectional"))
    )
    (net (code "50") (name "/LED_POWER_ON") (class "Default")
      (node (ref "R40") (pin "2") (pinfunction "2_2") (pintype "passive"))
      (node (ref "U3") (pin "90") (pinfunction "PG5_90") (pintype "bidirectional"))
    )
    (net (code "51") (name "/LED_STATUS1") (class "Default")
      (node (ref "R43") (pin "2") (pinfunction "2_2") (pintype "passive"))
      (node (ref "U3") (pin "81") (pinfunction "PD12_81") (pintype "bidirectional"))
    )
    (net (code "52") (name "/LED_STATUS2") (class "Default")
      (node (ref "R46") (pin "2") (pinfunction "2_2") (pintype "passive"))
      (node (ref "U3") (pin "80") (pinfunction "PD11_80") (pintype "bidirectional"))
    )
    (net (code "53") (name "/LED_STATUS3") (class "Default")
      (node (ref "R50") (pin "2") (pinfunction "2_2") (pintype "passive"))
      (node (ref "U3") (pin "79") (pinfunction "PD10_79") (pintype "bidirectional"))
    )
    (net (code "54") (name "/LED_STATUS4") (class "Default")
      (node (ref "R53") (pin "2") (pinfunction "2_2") (pintype "passive"))
      (node (ref "U3") (pin "78") (pinfunction "PD9_78") (pintype "bidirectional"))
    )
    (net (code "55") (name "/MISO") (class "Default")
      (node (ref "U3") (pin "112") (pinfunction "PC11_112") (pintype "bidirectional"))
    )
    (net (code "56") (name "/MOSI") (class "Default")
      (node (ref "U3") (pin "113") (pinfunction "PC12_113") (pintype "bidirectional"))
    )
    (net (code "57") (name "/MUX_A") (class "Default")
      (node (ref "U3") (pin "118") (pinfunction "PD4_118") (pintype "bidirectional"))
      (node (ref "U7") (pin "10") (pinfunction "A_10") (pintype "input"))
    )
    (net (code "58") (name "/MUX_B") (class "Default")
      (node (ref "U3") (pin "117") (pinfunction "PD3_117") (pintype "bidirectional"))
      (node (ref "U7") (pin "9") (pinfunction "B_9") (pintype "input"))
    )
    (net (code "59") (name "/NRST") (class "Default")
      (node (ref "C57") (pin "2") (pinfunction "2_2") (pintype "passive"))
      (node (ref "CN2") (pin "1") (pinfunction "1_1") (pintype "passive"))
      (node (ref "P23") (pin "6") (pinfunction "6_6") (pintype "passive"))
      (node (ref "R58") (pin "2") (pinfunction "2_2") (pintype "passive"))
      (node (ref "U3") (pin "25") (pinfunction "NRST_25") (pintype "bidirectional"))
    )
    (net (code "60") (name "/OC1") (class "Default")
      (node (ref "U4") (pin "4") (pinfunction "IN1-_4") (pintype "input"))
    )
    (net (code "61") (name "/OC2") (class "Default")
      (node (ref "U4") (pin "6") (pinfunction "IN2-_6") (pintype "input"))
    )
    (net (code "62") (name "/OC3") (class "Default")
      (node (ref "U4") (pin "8") (pinfunction "IN3-_8") (pintype "input"))
    )
    (net (code "63") (name "/OC4") (class "Default")
      (node (ref "U4") (pin "10") (pinfunction "IN4-_10") (pintype "input"))
    )
    (net (code "64") (name "/OC5") (class "Default")
      (node (ref "U5") (pin "2") (pinfunction "IN1-_2") (pintype "input"))
    )
    (net (code "65") (name "/OPTIONAL") (class "Default")
      (node (ref "U3") (pin "114") (pinfunction "PD0_114") (pintype "bidirectional"))
    )
    (net (code "66") (name "/SCK") (class "Default")
      (node (ref "U3") (pin "111") (pinfunction "PC10_111") (pintype "bidirectional"))
    )
    (net (code "67") (name "/SCL1") (class "Default")
      (node (ref "P24") (pin "3") (pinfunction "3_3") (pintype "passive"))
      (node (ref "R29") (pin "2") (pinfunction "2_2") (pintype "passive"))
      (node (ref "U3") (pin "129") (pinfunction "PG14_129") (pintype "bidirectional"))
    )
    (net (code "68") (name "/SCL2") (class "Default")
      (node (ref "R32") (pin "2") (pinfunction "2_2") (pintype "passive"))
      (node (ref "U3") (pin "11") (pinfunction "PF1_11") (pintype "bidirectional"))
    )
    (net (code "69") (name "/SDA1") (class "Default")
      (node (ref "P24") (pin "2") (pinfunction "2_2") (pintype "passive"))
      (node (ref "R30") (pin "2") (pinfunction "2_2") (pintype "passive"))
      (node (ref "U3") (pin "128") (pinfunction "PG13_128") (pintype "bidirectional"))
    )
    (net (code "70") (name "/SDA2") (class "Default")
      (node (ref "R31") (pin "2") (pinfunction "2_2") (pintype "passive"))
      (node (ref "U3") (pin "10") (pinfunction "PF0_10") (pintype "bidirectional"))
    )
    (net (code "71") (name "/SERVO1_EN") (class "Default")
      (node (ref "U3") (pin "69") (pinfunction "PB10_69") (pintype "bidirectional"))
    )
    (net (code "72") (name "/SERVO2_EN") (class "Default")
      (node (ref "U3") (pin "68") (pinfunction "PE15_68") (pintype "bidirectional"))
    )
    (net (code "73") (name "/SERVO3_EN") (class "Default")
      (node (ref "U3") (pin "67") (pinfunction "PE14_67") (pintype "bidirectional"))
    )
    (net (code "74") (name "/SERVO4_EN") (class "Default")
      (node (ref "U3") (pin "66") (pinfunction "PE13_66") (pintype "bidirectional"))
    )
    (net (code "75") (name "/SERVO5_EN") (class "Default")
      (node (ref "U3") (pin "65") (pinfunction "PE12_65") (pintype "bidirectional"))
    )
    (net (code "76") (name "/SERVO6_EN") (class "Default")
      (node (ref "U3") (pin "64") (pinfunction "PE11_64") (pintype "bidirectional"))
    )
    (net (code "77") (name "/SERVO7_EN") (class "Default")
      (node (ref "U3") (pin "63") (pinfunction "PE10_63") (pintype "bidirectional"))
    )
    (net (code "78") (name "/SERVO8_EN") (class "Default")
      (node (ref "U3") (pin "60") (pinfunction "PE9_60") (pintype "bidirectional"))
    )
    (net (code "79") (name "/SERVO9_EN") (class "Default")
      (node (ref "U3") (pin "59") (pinfunction "PE8_59") (pintype "bidirectional"))
    )
    (net (code "80") (name "/SERVO10_EN") (class "Default")
      (node (ref "U3") (pin "58") (pinfunction "PE7_58") (pintype "bidirectional"))
    )
    (net (code "81") (name "/SERVO11_EN") (class "Default")
      (node (ref "U3") (pin "57") (pinfunction "PG1_57") (pintype "bidirectional"))
    )
    (net (code "82") (name "/SERVO12_EN") (class "Default")
      (node (ref "U3") (pin "56") (pinfunction "PG0_56") (pintype "bidirectional"))
    )
    (net (code "83") (name "/SERVO13_EN") (class "Default")
      (node (ref "U3") (pin "55") (pinfunction "PF15_55") (pintype "bidirectional"))
    )
    (net (code "84") (name "/SERVO14_EN") (class "Default")
      (node (ref "U3") (pin "54") (pinfunction "PF14_54") (pintype "bidirectional"))
    )
    (net (code "85") (name "/SERVO15_EN") (class "Default")
      (node (ref "U3") (pin "53") (pinfunction "PF13_53") (pintype "bidirectional"))
    )
    (net (code "86") (name "/SERVO16_EN") (class "Default")
      (node (ref "U3") (pin "50") (pinfunction "PF12_50") (pintype "bidirectional"))
    )
    (net (code "87") (name "/SERVO17_EN") (class "Default")
      (node (ref "U3") (pin "49") (pinfunction "PF11_49") (pintype "bidirectional"))
    )
    (net (code "88") (name "/SERVO18_EN") (class "Default")
      (node (ref "U3") (pin "48") (pinfunction "PB2_48") (pintype "bidirectional"))
    )
    (net (code "89") (name "/SWCLK") (class "Default")
      (node (ref "P23") (pin "3") (pinfunction "3_3") (pintype "passive"))
      (node (ref "U3") (pin "109") (pinfunction "PA14(JTCK-SWCLK)_109") (pintype "bidirectional"))
    )
    (net (code "90") (name "/SWDIO") (class "Default")
      (node (ref "P23") (pin "4") (pinfunction "4_4") (pintype "passive"))
      (node (ref "U3") (pin "105") (pinfunction "PA13(JTMS-SWDIO)_105") (pintype "bidirectional"))
    )
    (net (code "91") (name "/SWO") (class "Default")
      (node (ref "P23") (pin "2") (pinfunction "2_2") (pintype "passive"))
      (node (ref "U3") (pin "133") (pinfunction "PB3(JTDO-TRACESWO)_133") (pintype "bidirectional"))
    )
    (net (code "92") (name "/SW_BAT_INDICATOR") (class "Default")
      (node (ref "C58") (pin "2") (pinfunction "2_2") (pintype "passive"))
      (node (ref "D26") (pin "1") (pinfunction "K_1") (pintype "passive"))
      (node (ref "R59") (pin "2") (pinfunction "2_2") (pintype "passive"))
      (node (ref "SW4") (pin "1") (pinfunction "1_1") (pintype "passive"))
      (node (ref "SW4") (pin "2") (pinfunction "2_2") (pintype "passive"))
      (node (ref "U3") (pin "93") (pinfunction "PG8_93") (pintype "bidirectional"))
    )
    (net (code "93") (name "/SW_CLR_ERR") (class "Default")
      (node (ref "C55") (pin "2") (pinfunction "2_2") (pintype "passive"))
      (node (ref "R39") (pin "2") (pinfunction "2_2") (pintype "passive"))
      (node (ref "SW2") (pin "1") (pinfunction "1_1") (pintype "passive"))
      (node (ref "SW2") (pin "2") (pinfunction "2_2") (pintype "passive"))
      (node (ref "U3") (pin "92") (pinfunction "PG7_92") (pintype "bidirectional"))
    )
    (net (code "94") (name "/SW_EMERGENCY") (class "Default")
      (node (ref "C52") (pin "2") (pinfunction "2_2") (pintype "passive"))
      (node (ref "P25") (pin "1") (pinfunction "1_1") (pintype "passive"))
      (node (ref "R36") (pin "2") (pinfunction "2_2") (pintype "passive"))
      (node (ref "U3") (pin "123") (pinfunction "PD7_123") (pintype "bidirectional"))
    )
    (net (code "95") (name "/SW_FUNC") (class "Default")
      (node (ref "C56") (pin "2") (pinfunction "2_2") (pintype "passive"))
      (node (ref "R49") (pin "2") (pinfunction "2_2") (pintype "passive"))
      (node (ref "SW3") (pin "1") (pinfunction "1_1") (pintype "passive"))
      (node (ref "SW3") (pin "2") (pinfunction "2_2") (pintype "passive"))
      (node (ref "U3") (pin "91") (pinfunction "PG6_91") (pintype "bidirectional"))
    )
    (net (code "96") (name "/SW_POWER_ON") (class "Default")
      (node (ref "C51") (pin "2") (pinfunction "2_2") (pintype "passive"))
      (node (ref "D26") (pin "2") (pinfunction "A_2") (pintype "passive"))
      (node (ref "P26") (pin "1") (pinfunction "1_1") (pintype "passive"))
      (node (ref "R35") (pin "2") (pinfunction "2_2") (pintype "passive"))
      (node (ref "SW1") (pin "1") (pinfunction "1_1") (pintype "passive"))
      (node (ref "SW1") (pin "2") (pinfunction "2_2") (pintype "passive"))
      (node (ref "U3") (pin "7") (pinfunction "PC13_7") (pintype "bidirectional"))
    )
    (net (code "97") (name "/U_TEMP") (class "Default")
      (node (ref "U3") (pin "13") (pinfunction "PF3_13") (pintype "bidirectional"))
      (node (ref "U7") (pin "3") (pinfunction "2-COM_3") (pintype "bidirectional"))
    )
    (net (code "98") (name "/U_TEMP1") (class "Default")
      (node (ref "U7") (pin "1") (pinfunction "2Y0_1") (pintype "bidirectional"))
    )
    (net (code "99") (name "/U_TEMP2") (class "Default")
      (node (ref "U7") (pin "5") (pinfunction "2Y1_5") (pintype "bidirectional"))
    )
    (net (code "100") (name "/U_TEMP3") (class "Default")
      (node (ref "U7") (pin "2") (pinfunction "2Y2_2") (pintype "bidirectional"))
    )
    (net (code "101") (name "/U_TEMP4") (class "Default")
      (node (ref "U7") (pin "4") (pinfunction "2Y3_4") (pintype "bidirectional"))
    )
    (net (code "102") (name "/VOLTAGE_EN") (class "Default")
      (node (ref "U3") (pin "12") (pinfunction "PF2_12") (pintype "bidirectional"))
    )
    (net (code "103") (name "/V_OUT_EN1") (class "Default")
      (node (ref "U3") (pin "139") (pinfunction "PB8_139") (pintype "bidirectional"))
    )
    (net (code "104") (name "/V_OUT_EN2") (class "Default")
      (node (ref "U3") (pin "136") (pinfunction "PB6_136") (pintype "bidirectional"))
    )
    (net (code "105") (name "/V_OUT_EN3") (class "Default")
      (node (ref "U3") (pin "135") (pinfunction "PB5_135") (pintype "bidirectional"))
    )
    (net (code "106") (name "/V_OUT_EN4") (class "Default")
      (node (ref "U3") (pin "127") (pinfunction "PG12_127") (pintype "bidirectional"))
    )
    (net (code "107") (name "/V_OUT_EN5") (class "Default")
      (node (ref "U3") (pin "126") (pinfunction "PG11_126") (pintype "bidirectional"))
    )
    (net (code "108") (name "/V_OUT_EN6") (class "Default")
      (node (ref "U3") (pin "125") (pinfunction "PG10_125") (pintype "bidirectional"))
    )
    (net (code "114") (name "3,3VC") (class "Default")
      (node (ref "C26") (pin "2") (pinfunction "2_2") (pintype "passive"))
      (node (ref "C32") (pin "2") (pinfunction "2_2") (pintype "passive"))
      (node (ref "C50") (pin "2") (pinfunction "2_2") (pintype "passive"))
      (node (ref "P24") (pin "4") (pinfunction "4_4") (pintype "passive"))
      (node (ref "R12") (pin "2") (pinfunction "2_2") (pintype "passive"))
      (node (ref "R13") (pin "2") (pinfunction "2_2") (pintype "passive"))
      (node (ref "R14") (pin "2") (pinfunction "2_2") (pintype "passive"))
      (node (ref "R21") (pin "2") (pinfunction "2_2") (pintype "passive"))
      (node (ref "R22") (pin "2") (pinfunction "2_2") (pintype "passive"))
      (node (ref "U4") (pin "3") (pinfunction "V+_3") (pintype "power_in"))
      (node (ref "U5") (pin "8") (pinfunction "V+_8") (pintype "power_in"))
      (node (ref "U7") (pin "16") (pinfunction "VCC_16") (pintype "power_in"))
    )
    (net (code "115") (name "3,3V_STANDBY") (class "Default")
      (node (ref "C33") (pin "2") (pinfunction "2_2") (pintype "passive"))
      (node (ref "C34") (pin "2") (pinfunction "2_2") (pintype "passive"))
      (node (ref "C35") (pin "2") (pinfunction "2_2") (pintype "passive"))
      (node (ref "C36") (pin "2") (pinfunction "2_2") (pintype "passive"))
      (node (ref "C37") (pin "2") (pinfunction "2_2") (pintype "passive"))
      (node (ref "C38") (pin "2") (pinfunction "2_2") (pintype "passive"))
      (node (ref "C39") (pin "2") (pinfunction "2_2") (pintype "passive"))
      (node (ref "C40") (pin "2") (pinfunction "2_2") (pintype "passive"))
      (node (ref "C41") (pin "2") (pinfunction "2_2") (pintype "passive"))
      (node (ref "C42") (pin "2") (pinfunction "2_2") (pintype "passive"))
      (node (ref "C43") (pin "2") (pinfunction "2_2") (pintype "passive"))
      (node (ref "C44") (pin "2") (pinfunction "2_2") (pintype "passive"))
      (node (ref "C45") (pin "2") (pinfunction "2_2") (pintype "passive"))
      (node (ref "C46") (pin "2") (pinfunction "2_2") (pintype "passive"))
      (node (ref "C47") (pin "2") (pinfunction "2_2") (pintype "passive"))
      (node (ref "C48") (pin "2") (pinfunction "2_2") (pintype "passive"))
      (node (ref "C49") (pin "2") (pinfunction "2_2") (pintype "passive"))
      (node (ref "P22") (pin "4") (pinfunction "4_4") (pintype "passive"))
      (node (ref "P23") (pin "1") (pinfunction "1_1") (pintype "passive"))
      (node (ref "R29") (pin "1") (pinfunction "1_1") (pintype "passive"))
      (node (ref "R30") (pin "1") (pinfunction "1_1") (pintype "passive"))
      (node (ref "R31") (pin "1") (pinfunction "1_1") (pintype "passive"))
      (node (ref "R32") (pin "1") (pinfunction "1_1") (pintype "passive"))
      (node (ref "R35") (pin "1") (pinfunction "1_1") (pintype "passive"))
      (node (ref "R36") (pin "1") (pinfunction "1_1") (pintype "passive"))
      (node (ref "R39") (pin "1") (pinfunction "1_1") (pintype "passive"))
      (node (ref "R49") (pin "1") (pinfunction "1_1") (pintype "passive"))
      (node (ref "R58") (pin "1") (pinfunction "1_1") (pintype "passive"))
      (node (ref "R59") (pin "1") (pinfunction "1_1") (pintype "passive"))
      (node (ref "U3") (pin "106") (pinfunction "VDDUSB_106") (pintype "power_in"))
      (node (ref "U3") (pin "108") (pinfunction "VDD_108") (pintype "power_in"))
      (node (ref "U3") (pin "121") (pinfunction "VDD_121") (pintype "power_in"))
      (node (ref "U3") (pin "131") (pinfunction "VDDIO2_131") (pintype "power_in"))
      (node (ref "U3") (pin "144") (pinfunction "VDD_144") (pintype "power_in"))
      (node (ref "U3") (pin "17") (pinfunction "VDD_17") (pintype "power_in"))
      (node (ref "U3") (pin "33") (pinfunction "VDDA_33") (pintype "power_in"))
      (node (ref "U3") (pin "39") (pinfunction "VDD_39") (pintype "power_in"))
      (node (ref "U3") (pin "52") (pinfunction "VDD_52") (pintype "power_in"))
      (node (ref "U3") (pin "6") (pinfunction "VBAT_6") (pintype "power_in"))
      (node (ref "U3") (pin "62") (pinfunction "VDD_62") (pintype "power_in"))
      (node (ref "U3") (pin "72") (pinfunction "VDD_72") (pintype "power_in"))
      (node (ref "U3") (pin "84") (pinfunction "VDD_84") (pintype "power_in"))
      (node (ref "U3") (pin "95") (pinfunction "VDDIO2_95") (pintype "power_in"))
      (node (ref "U6") (pin "3") (pinfunction "VCC_3") (pintype "power_in"))
    )
    (net (code "116") (name "5V_STANDBY") (class "Default")
      (node (ref "FB2") (pin "1") (pinfunction "1_1") (pintype "passive"))
      (node (ref "IC1") (pin "2") (pinfunction "S_2") (pintype "passive"))
      (node (ref "R28") (pin "1") (pinfunction "1_1") (pintype "passive"))
    )
    (net (code "117") (name "AGND") (class "Default")
      (node (ref "C28") (pin "1") (pinfunction "1_1") (pintype "passive"))
      (node (ref "C29") (pin "1") (pinfunction "1_1") (pintype "passive"))
      (node (ref "C30") (pin "1") (pinfunction "1_1") (pintype "passive"))
      (node (ref "C31") (pin "1") (pinfunction "1_1") (pintype "passive"))
      (node (ref "U2") (pin "3") (pinfunction "GND_3") (pintype "passive"))
      (node (ref "U3") (pin "31") (pinfunction "VREF-_31") (pintype "power_in"))
    )
    (net (code "118") (name "GND") (class "Default")
      (node (ref "B1") (pin "2") (pinfunction "2_2") (pintype "passive"))
      (node (ref "C26") (pin "1") (pinfunction "1_1") (pintype "passive"))
      (node (ref "C27") (pin "1") (pinfunction "1_1") (pintype "passive"))
      (node (ref "C32") (pin "1") (pinfunction "1_1") (pintype "passive"))
      (node (ref "C33") (pin "1") (pinfunction "1_1") (pintype "passive"))
      (node (ref "C34") (pin "1") (pinfunction "1_1") (pintype "passive"))
      (node (ref "C35") (pin "1") (pinfunction "1_1") (pintype "passive"))
      (node (ref "C36") (pin "1") (pinfunction "1_1") (pintype "passive"))
      (node (ref "C37") (pin "1") (pinfunction "1_1") (pintype "passive"))
      (node (ref "C38") (pin "1") (pinfunction "1_1") (pintype "passive"))
      (node (ref "C39") (pin "1") (pinfunction "1_1") (pintype "passive"))
      (node (ref "C40") (pin "1") (pinfunction "1_1") (pintype "passive"))
      (node (ref "C41") (pin "1") (pinfunction "1_1") (pintype "passive"))
      (node (ref "C42") (pin "1") (pinfunction "1_1") (pintype "passive"))
      (node (ref "C43") (pin "1") (pinfunction "1_1") (pintype "passive"))
      (node (ref "C44") (pin "1") (pinfunction "1_1") (pintype "passive"))
      (node (ref "C45") (pin "1") (pinfunction "1_1") (pintype "passive"))
      (node (ref "C46") (pin "1") (pinfunction "1_1") (pintype "passive"))
      (node (ref "C47") (pin "1") (pinfunction "1_1") (pintype "passive"))
      (node (ref "C48") (pin "1") (pinfunction "1_1") (pintype "passive"))
      (node (ref "C49") (pin "1") (pinfunction "1_1") (pintype "passive"))
      (node (ref "C50") (pin "1") (pinfunction "1_1") (pintype "passive"))
      (node (ref "C51") (pin "1") (pinfunction "1_1") (pintype "passive"))
      (node (ref "C52") (pin "1") (pinfunction "1_1") (pintype "passive"))
      (node (ref "C53") (pin "1") (pinfunction "1_1") (pintype "passive"))
      (node (ref "C54") (pin "1") (pinfunction "1_1") (pintype "passive"))
      (node (ref "C55") (pin "1") (pinfunction "1_1") (pintype "passive"))
      (node (ref "C56") (pin "1") (pinfunction "1_1") (pintype "passive"))
      (node (ref "C57") (pin "1") (pinfunction "1_1") (pintype "passive"))
      (node (ref "C58") (pin "1") (pinfunction "1_1") (pintype "passive"))
      (node (ref "CN2") (pin "2") (pinfunction "2_2") (pintype "passive"))
      (node (ref "D10") (pin "2") (pinfunction "K_2") (pintype "passive"))
      (node (ref "D11") (pin "2") (pinfunction "K_2") (pintype "passive"))
      (node (ref "D12") (pin "2") (pinfunction "K_2") (pintype "passive"))
      (node (ref "D13") (pin "2") (pinfunction "K_2") (pintype "passive"))
      (node (ref "D14") (pin "2") (pinfunction "K_2") (pintype "passive"))
      (node (ref "D15") (pin "2") (pinfunction "K_2") (pintype "passive"))
      (node (ref "D16") (pin "2") (pinfunction "K_2") (pintype "passive"))
      (node (ref "D17") (pin "2") (pinfunction "K_2") (pintype "passive"))
      (node (ref "D18") (pin "2") (pinfunction "K_2") (pintype "passive"))
      (node (ref "D19") (pin "2") (pinfunction "K_2") (pintype "passive"))
      (node (ref "D20") (pin "2") (pinfunction "K_2") (pintype "passive"))
      (node (ref "D21") (pin "2") (pinfunction "K_2") (pintype "passive"))
      (node (ref "D22") (pin "2") (pinfunction "K_2") (pintype "passive"))
      (node (ref "D23") (pin "2") (pinfunction "K_2") (pintype "passive"))
      (node (ref "D24") (pin "2") (pinfunction "K_2") (pintype "passive"))
      (node (ref "D25") (pin "2") (pinfunction "K_2") (pintype "passive"))
      (node (ref "D9") (pin "1") (pinfunction "1_1") (pintype "passive"))
      (node (ref "P21") (pin "2") (pinfunction "2_2") (pintype "passive"))
      (node (ref "P22") (pin "1") (pinfunction "1_1") (pintype "passive"))
      (node (ref "P23") (pin "5") (pinfunction "5_5") (pintype "passive"))
      (node (ref "P24") (pin "1") (pinfunction "1_1") (pintype "passive"))
      (node (ref "P25") (pin "2") (pinfunction "2_2") (pintype "passive"))
      (node (ref "P26") (pin "2") (pinfunction "2_2") (pintype "passive"))
      (node (ref "Q5") (pin "2") (pinfunction "SOURCE_2") (pintype "passive"))
      (node (ref "R15") (pin "2") (pinfunction "2_2") (pintype "passive"))
      (node (ref "R16") (pin "2") (pinfunction "2_2") (pintype "passive"))
      (node (ref "R17") (pin "2") (pinfunction "2_2") (pintype "passive"))
      (node (ref "R23") (pin "2") (pinfunction "2_2") (pintype "passive"))
      (node (ref "R24") (pin "2") (pinfunction "2_2") (pintype "passive"))
      (node (ref "R42") (pin "2") (pinfunction "2_2") (pintype "passive"))
      (node (ref "SW1") (pin "3") (pinfunction "3_3") (pintype "passive"))
      (node (ref "SW1") (pin "4") (pinfunction "4_4") (pintype "passive"))
      (node (ref "SW2") (pin "3") (pinfunction "3_3") (pintype "passive"))
      (node (ref "SW2") (pin "4") (pinfunction "4_4") (pintype "passive"))
      (node (ref "SW3") (pin "3") (pinfunction "3_3") (pintype "passive"))
      (node (ref "SW3") (pin "4") (pinfunction "4_4") (pintype "passive"))
      (node (ref "SW4") (pin "3") (pinfunction "3_3") (pintype "passive"))
      (node (ref "SW4") (pin "4") (pinfunction "4_4") (pintype "passive"))
      (node (ref "U3") (pin "107") (pinfunction "VSS_107") (pintype "power_in"))
      (node (ref "U3") (pin "120") (pinfunction "VSS_120") (pintype "power_in"))
      (node (ref "U3") (pin "130") (pinfunction "VSS_130") (pintype "power_in"))
      (node (ref "U3") (pin "143") (pinfunction "VSS_143") (pintype "power_in"))
      (node (ref "U3") (pin "16") (pinfunction "VSS_16") (pintype "power_in"))
      (node (ref "U3") (pin "30") (pinfunction "VSSA_30") (pintype "power_in"))
      (node (ref "U3") (pin "38") (pinfunction "VSS_38") (pintype "power_in"))
      (node (ref "U3") (pin "51") (pinfunction "VSS_51") (pintype "power_in"))
      (node (ref "U3") (pin "61") (pinfunction "VSS_61") (pintype "power_in"))
      (node (ref "U3") (pin "71") (pinfunction "VSS_71") (pintype "power_in"))
      (node (ref "U3") (pin "83") (pinfunction "VSS_83") (pintype "power_in"))
      (node (ref "U3") (pin "94") (pinfunction "VSS_94") (pintype "power_in"))
      (node (ref "U4") (pin "12") (pinfunction "GND_12") (pintype "power_in"))
      (node (ref "U5") (pin "4") (pinfunction "GND_4") (pintype "power_in"))
      (node (ref "U6") (pin "2") (pinfunction "GND_2") (pintype "power_in"))
      (node (ref "U7") (pin "6") (pinfunction "INH_6") (pintype "input"))
      (node (ref "U7") (pin "7") (pinfunction "GND_7") (pintype "power_in"))
      (node (ref "U7") (pin "8") (pinfunction "GND_8") (pintype "power_in"))
      (node (ref "Y1") (pin "2") (pinfunction "GND_2") (pintype "passive"))
      (node (ref "Y1") (pin "4") (pinfunction "GND_4") (pintype "passive"))
    )
    (net (code "119") (name "Net-(B1-Pad1)") (class "Default")
      (node (ref "B1") (pin "1") (pinfunction "1_1") (pintype "passive"))
      (node (ref "R37") (pin "2") (pinfunction "2_2") (pintype "passive"))
    )
    (net (code "120") (name "Net-(C53-Pad2)") (class "Default")
      (node (ref "C53") (pin "2") (pinfunction "2_2") (pintype "passive"))
      (node (ref "R38") (pin "1") (pinfunction "1_1") (pintype "passive"))
      (node (ref "Y1") (pin "1") (pinfunction "OSC_1") (pintype "passive"))
    )
    (net (code "121") (name "Net-(D10-A)") (class "Default")
      (node (ref "D10") (pin "1") (pinfunction "A_1") (pintype "passive"))
      (node (ref "R40") (pin "1") (pinfunction "1_1") (pintype "passive"))
    )
    (net (code "122") (name "Net-(D11-A)") (class "Default")
      (node (ref "D11") (pin "1") (pinfunction "A_1") (pintype "passive"))
      (node (ref "R41") (pin "1") (pinfunction "1_1") (pintype "passive"))
    )
    (net (code "123") (name "Net-(D12-A)") (class "Default")
      (node (ref "D12") (pin "1") (pinfunction "A_1") (pintype "passive"))
      (node (ref "R43") (pin "1") (pinfunction "1_1") (pintype "passive"))
    )
    (net (code "124") (name "Net-(D13-A)") (class "Default")
      (node (ref "D13") (pin "1") (pinfunction "A_1") (pintype "passive"))
      (node (ref "R44") (pin "1") (pinfunction "1_1") (pintype "passive"))
    )
    (net (code "125") (name "Net-(D14-A)") (class "Default")
      (node (ref "D14") (pin "1") (pinfunction "A_1") (pintype "passive"))
      (node (ref "R45") (pin "1") (pinfunction "1_1") (pintype "passive"))
    )
    (net (code "126") (name "Net-(D15-A)") (class "Default")
      (node (ref "D15") (pin "1") (pinfunction "A_1") (pintype "passive"))
      (node (ref "R46") (pin "1") (pinfunction "1_1") (pintype "passive"))
    )
    (net (code "127") (name "Net-(D16-A)") (class "Default")
      (node (ref "D16") (pin "1") (pinfunction "A_1") (pintype "passive"))
      (node (ref "R47") (pin "1") (pinfunction "1_1") (pintype "passive"))
    )
    (net (code "128") (name "Net-(D17-A)") (class "Default")
      (node (ref "D17") (pin "1") (pinfunction "A_1") (pintype "passive"))
      (node (ref "R48") (pin "1") (pinfunction "1_1") (pintype "passive"))
    )
    (net (code "129") (name "Net-(D18-A)") (class "Default")
      (node (ref "D18") (pin "1") (pinfunction "A_1") (pintype "passive"))
      (node (ref "R50") (pin "1") (pinfunction "1_1") (pintype "passive"))
    )
    (net (code "130") (name "Net-(D19-A)") (class "Default")
      (node (ref "D19") (pin "1") (pinfunction "A_1") (pintype "passive"))
      (node (ref "R51") (pin "1") (pinfunction "1_1") (pintype "passive"))
    )
    (net (code "131") (name "Net-(D20-A)") (class "Default")
      (node (ref "D20") (pin "1") (pinfunction "A_1") (pintype "passive"))
      (node (ref "R52") (pin "1") (pinfunction "1_1") (pintype "passive"))
    )
    (net (code "132") (name "Net-(D21-A)") (class "Default")
      (node (ref "D21") (pin "1") (pinfunction "A_1") (pintype "passive"))
      (node (ref "R53") (pin "1") (pinfunction "1_1") (pintype "passive"))
    )
    (net (code "133") (name "Net-(D22-A)") (class "Default")
      (node (ref "D22") (pin "1") (pinfunction "A_1") (pintype "passive"))
      (node (ref "R54") (pin "1") (pinfunction "1_1") (pintype "passive"))
    )
    (net (code "134") (name "Net-(D23-A)") (class "Default")
      (node (ref "D23") (pin "1") (pinfunction "A_1") (pintype "passive"))
      (node (ref "R55") (pin "1") (pinfunction "1_1") (pintype "passive"))
    )
    (net (code "135") (name "Net-(D24-A)") (class "Default")
      (node (ref "D24") (pin "1") (pinfunction "A_1") (pintype "passive"))
      (node (ref "R56") (pin "1") (pinfunction "1_1") (pintype "passive"))
    )
    (net (code "136") (name "Net-(D25-A)") (class "Default")
      (node (ref "D25") (pin "1") (pinfunction "A_1") (pintype "passive"))
      (node (ref "R57") (pin "1") (pinfunction "1_1") (pintype "passive"))
    )
    (net (code "137") (name "Net-(IC1-D)") (class "Default")
      (node (ref "D9") (pin "2") (pinfunction "2_2") (pintype "passive"))
      (node (ref "IC1") (pin "3") (pinfunction "D_3") (pintype "passive"))
      (node (ref "P21") (pin "1") (pinfunction "1_1") (pintype "passive"))
    )
    (net (code "138") (name "Net-(IC1-G)") (class "Default")
      (node (ref "IC1") (pin "1") (pinfunction "G_1") (pintype "passive"))
      (node (ref "R28") (pin "2") (pinfunction "2_2") (pintype "passive"))
      (node (ref "R33") (pin "1") (pinfunction "1_1") (pintype "passive"))
    )
    (net (code "139") (name "Net-(Q5-DRAIN)") (class "Default")
      (node (ref "Q5") (pin "3") (pinfunction "DRAIN_3") (pintype "passive"))
      (node (ref "R33") (pin "2") (pinfunction "2_2") (pintype "passive"))
    )
    (net (code "140") (name "Net-(Q5-GATE)") (class "Default")
      (node (ref "Q5") (pin "1") (pinfunction "GATE_1") (pintype "passive"))
      (node (ref "R34") (pin "2") (pinfunction "2_2") (pintype "passive"))
    )
    (net (code "141") (name "Net-(U2-VIN)") (class "Default")
      (node (ref "C27") (pin "2") (pinfunction "2_2") (pintype "passive"))
      (node (ref "C28") (pin "2") (pinfunction "2_2") (pintype "passive"))
      (node (ref "FB2") (pin "2") (pinfunction "2_2") (pintype "passive"))
      (node (ref "U2") (pin "1") (pinfunction "VIN_1") (pintype "passive"))
    )
    (net (code "142") (name "Net-(U2-VOUT)") (class "Default")
      (node (ref "C29") (pin "2") (pinfunction "2_2") (pintype "passive"))
      (node (ref "C30") (pin "2") (pinfunction "2_2") (pintype "passive"))
      (node (ref "C31") (pin "2") (pinfunction "2_2") (pintype "passive"))
      (node (ref "U2") (pin "2") (pinfunction "VOUT_2") (pintype "passive"))
      (node (ref "U3") (pin "32") (pinfunction "VREF+_32") (pintype "power_in"))
    )
    (net (code "143") (name "Net-(U3B-BOOT0)") (class "Default")
      (node (ref "R42") (pin "1") (pinfunction "1_1") (pintype "passive"))
      (node (ref "U3") (pin "138") (pinfunction "BOOT0_138") (pintype "input"))
    )
    (net (code "144") (name "Net-(U3B-PH0-OSC_IN(PH0))") (class "Default")
      (node (ref "C54") (pin "2") (pinfunction "2_2") (pintype "passive"))
      (node (ref "U3") (pin "23") (pinfunction "PH0-OSC_IN(PH0)_23") (pintype "bidirectional"))
      (node (ref "Y1") (pin "3") (pinfunction "OSC_3") (pintype "passive"))
    )
    (net (code "145") (name "Net-(U3B-PH1-OSC_OUT(PH1))") (class "Default")
      (node (ref "R38") (pin "2") (pinfunction "2_2") (pintype "passive"))
      (node (ref "U3") (pin "24") (pinfunction "PH1-OSC_OUT(PH1)_24") (pintype "bidirectional"))
    )
    (net (code "146") (name "Net-(U4A-IN1+)") (class "Default")
      (node (ref "R12") (pin "1") (pinfunction "1_1") (pintype "passive"))
      (node (ref "R15") (pin "1") (pinfunction "1_1") (pintype "passive"))
      (node (ref "R18") (pin "1") (pinfunction "1_1") (pintype "passive"))
      (node (ref "U4") (pin "5") (pinfunction "IN1+_5") (pintype "input"))
    )
    (net (code "147") (name "Net-(U4B-IN2+)") (class "Default")
      (node (ref "R13") (pin "1") (pinfunction "1_1") (pintype "passive"))
      (node (ref "R16") (pin "1") (pinfunction "1_1") (pintype "passive"))
      (node (ref "R19") (pin "2") (pinfunction "2_2") (pintype "passive"))
      (node (ref "U4") (pin "7") (pinfunction "IN2+_7") (pintype "input"))
    )
    (net (code "148") (name "Net-(U4C-IN3+)") (class "Default")
      (node (ref "R14") (pin "1") (pinfunction "1_1") (pintype "passive"))
      (node (ref "R17") (pin "1") (pinfunction "1_1") (pintype "passive"))
      (node (ref "R20") (pin "2") (pinfunction "2_2") (pintype "passive"))
      (node (ref "U4") (pin "9") (pinfunction "IN3+_9") (pintype "input"))
    )
    (net (code "149") (name "Net-(U4D-IN4+)") (class "Default")
      (node (ref "R21") (pin "1") (pinfunction "1_1") (pintype "passive"))
      (node (ref "R23") (pin "1") (pinfunction "1_1") (pintype "passive"))
      (node (ref "R25") (pin "2") (pinfunction "2_2") (pintype "passive"))
      (node (ref "U4") (pin "11") (pinfunction "IN4+_11") (pintype "input"))
    )
    (net (code "150") (name "Net-(U5A-IN1+)") (class "Default")
      (node (ref "R22") (pin "1") (pinfunction "1_1") (pintype "passive"))
      (node (ref "R24") (pin "1") (pinfunction "1_1") (pintype "passive"))
      (node (ref "R26") (pin "2") (pinfunction "2_2") (pintype "passive"))
      (node (ref "U5") (pin "3") (pinfunction "IN1+_3") (pintype "input"))
    )
    (net (code "151") (name "unconnected-(U3A-PA8-Pad100)") (class "Default")
      (node (ref "U3") (pin "100") (pinfunction "PA8_100") (pintype "bidirectional"))
    )
    (net (code "152") (name "unconnected-(U3A-PA9-Pad101)") (class "Default")
      (node (ref "U3") (pin "101") (pinfunction "PA9_101") (pintype "bidirectional"))
    )
    (net (code "153") (name "unconnected-(U3A-PA10-Pad102)") (class "Default")
      (node (ref "U3") (pin "102") (pinfunction "PA10_102") (pintype "bidirectional"))
    )
    (net (code "154") (name "unconnected-(U3A-PA15(JTDI)-Pad110)") (class "Default")
      (node (ref "U3") (pin "110") (pinfunction "PA15(JTDI)_110") (pintype "bidirectional"))
    )
    (net (code "155") (name "unconnected-(U3A-PB4(NJTRST)-Pad134)") (class "Default")
      (node (ref "U3") (pin "134") (pinfunction "PB4(NJTRST)_134") (pintype "bidirectional"))
    )
    (net (code "156") (name "unconnected-(U3A-PB7-Pad137)") (class "Default")
      (node (ref "U3") (pin "137") (pinfunction "PB7_137") (pintype "bidirectional"))
    )
    (net (code "157") (name "unconnected-(U3A-PB12-Pad73)") (class "Default")
      (node (ref "U3") (pin "73") (pinfunction "PB12_73") (pintype "bidirectional"))
    )
    (net (code "158") (name "unconnected-(U3A-PC6-Pad96)") (class "Default")
      (node (ref "U3") (pin "96") (pinfunction "PC6_96") (pintype "bidirectional"))
    )
    (net (code "159") (name "unconnected-(U3A-PC7-Pad97)") (class "Default")
      (node (ref "U3") (pin "97") (pinfunction "PC7_97") (pintype "bidirectional"))
    )
    (net (code "160") (name "unconnected-(U3A-PC8-Pad98)") (class "Default")
      (node (ref "U3") (pin "98") (pinfunction "PC8_98") (pintype "bidirectional"))
    )
    (net (code "161") (name "unconnected-(U3A-PD1-Pad115)") (class "Default")
      (node (ref "U3") (pin "115") (pinfunction "PD1_115") (pintype "bidirectional"))
    )
    (net (code "162") (name "unconnected-(U3A-PD2-Pad116)") (class "Default")
      (node (ref "U3") (pin "116") (pinfunction "PD2_116") (pintype "bidirectional"))
    )
    (net (code "163") (name "unconnected-(U3A-PD5-Pad119)") (class "Default")
      (node (ref "U3") (pin "119") (pinfunction "PD5_119") (pintype "bidirectional"))
    )
    (net (code "164") (name "unconnected-(U3A-PD6-Pad122)") (class "Default")
      (node (ref "U3") (pin "122") (pinfunction "PD6_122") (pintype "bidirectional"))
    )
    (net (code "165") (name "unconnected-(U3A-PE2-Pad1)") (class "Default")
      (node (ref "U3") (pin "1") (pinfunction "PE2_1") (pintype "bidirectional"))
    )
    (net (code "166") (name "unconnected-(U3A-PE4-Pad3)") (class "Default")
      (node (ref "U3") (pin "3") (pinfunction "PE4_3") (pintype "bidirectional"))
    )
    (net (code "167") (name "unconnected-(U3A-PE5-Pad4)") (class "Default")
      (node (ref "U3") (pin "4") (pinfunction "PE5_4") (pintype "bidirectional"))
    )
    (net (code "168") (name "unconnected-(U3A-PE6-Pad5)") (class "Default")
      (node (ref "U3") (pin "5") (pinfunction "PE6_5") (pintype "bidirectional"))
    )
    (net (code "169") (name "unconnected-(U3A-PF7-Pad19)") (class "Default")
      (node (ref "U3") (pin "19") (pinfunction "PF7_19") (pintype "bidirectional"))
    )
    (net (code "170") (name "unconnected-(U3B-PG9-Pad124)") (class "Default")
      (node (ref "U3") (pin "124") (pinfunction "PG9_124") (pintype "bidirectional"))
    )
    (net (code "171") (name "unconnected-(U3B-PG15-Pad132)") (class "Default")
      (node (ref "U3") (pin "132") (pinfunction "PG15_132") (pintype "bidirectional"))
    )
    (net (code "172") (name "unconnected-(U5B-IN2+-Pad5)") (class "Default")
      (node (ref "U5") (pin "5") (pinfunction "IN2+_5") (pintype "input+no_connect"))
    )
    (net (code "173") (name "unconnected-(U5B-IN2--Pad6)") (class "Default")
      (node (ref "U5") (pin "6") (pinfunction "IN2-_6") (pintype "input+no_connect"))
    )
    (net (code "174") (name "unconnected-(U5B-OUT2-Pad7)") (class "Default")
      (node (ref "U5") (pin "7") (pinfunction "OUT2_7") (pintype "output+no_connect"))
    )
    (net (code "175") (name "unconnected-(U6-NC-Pad5)") (class "Default")
      (node (ref "U6") (pin "5") (pinfunction "NC_5") (pintype "passive+no_connect"))
    )
    (net (code "176") (name "unconnected-(U6-NC-Pad8)") (class "Default")
      (node (ref "U6") (pin "8") (pinfunction "NC_8") (pintype "passive+no_connect"))
    )
    (net (code "177") (name "unconnected-(U7-1-COM-Pad13)") (class "Default")
      (node (ref "U7") (pin "13") (pinfunction "1-COM_13") (pintype "bidirectional+no_connect"))
    )
    (net (code "178") (name "unconnected-(U7-1Y0-Pad12)") (class "Default")
      (node (ref "U7") (pin "12") (pinfunction "1Y0_12") (pintype "bidirectional+no_connect"))
    )
    (net (code "179") (name "unconnected-(U7-1Y1-Pad14)") (class "Default")
      (node (ref "U7") (pin "14") (pinfunction "1Y1_14") (pintype "bidirectional+no_connect"))
    )
    (net (code "180") (name "unconnected-(U7-1Y2-Pad15)") (class "Default")
      (node (ref "U7") (pin "15") (pinfunction "1Y2_15") (pintype "bidirectional+no_connect"))
    )
    (net (code "181") (name "unconnected-(U7-1Y3-Pad11)") (class "Default")
      (node (ref "U7") (pin "11") (pinfunction "1Y3_11") (pintype "bidirectional+no_connect"))
    )
  )
)
